# M7104B.net
KiCad netlist of a schematic drawn in EAGLE
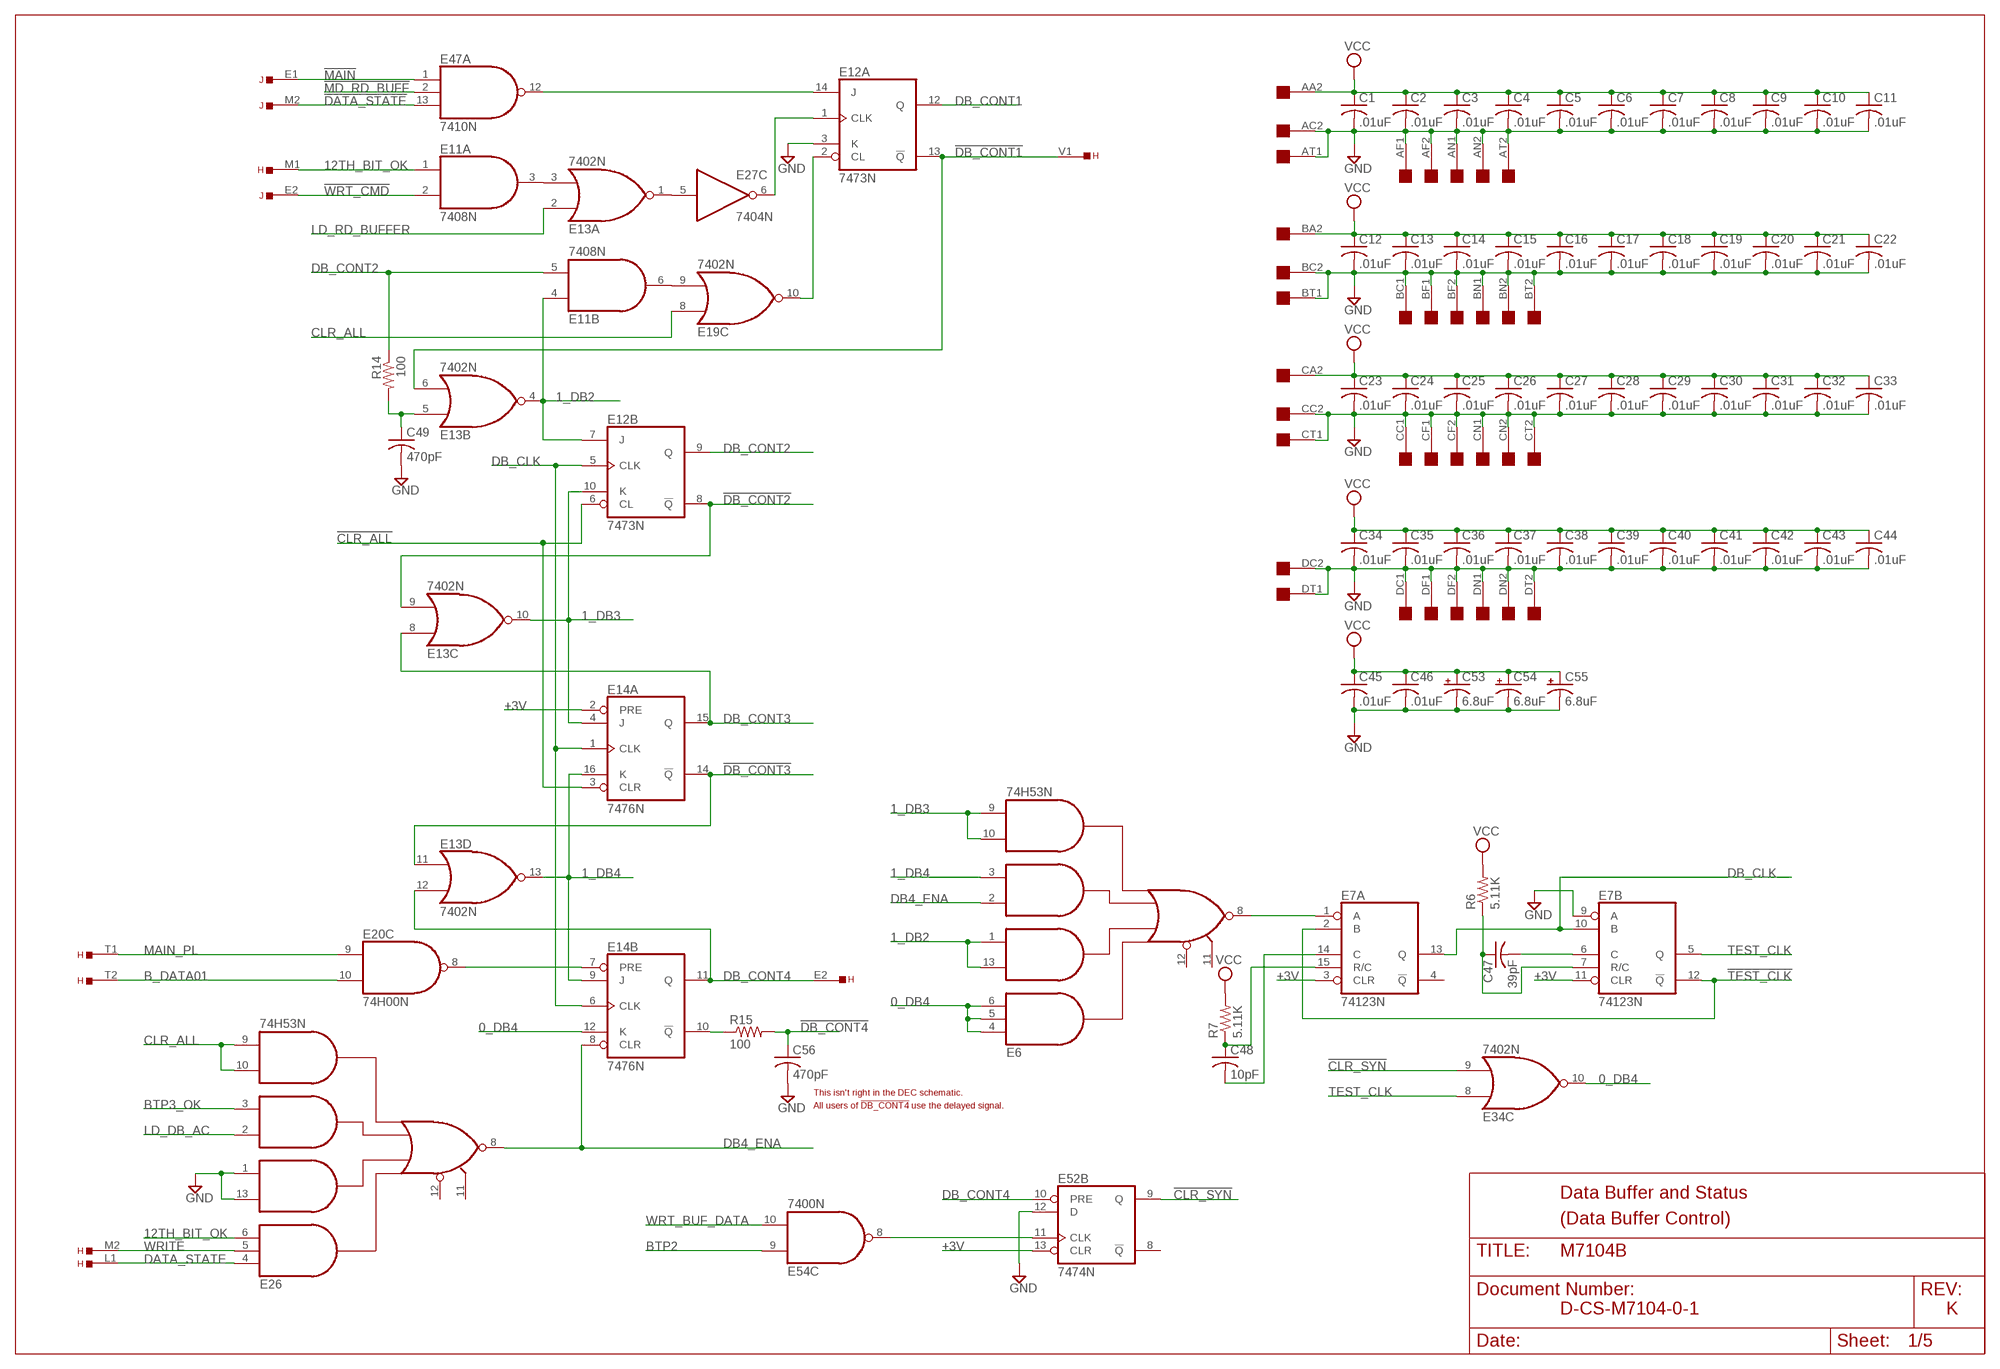
[diagram p0: schematic, sheet 1]
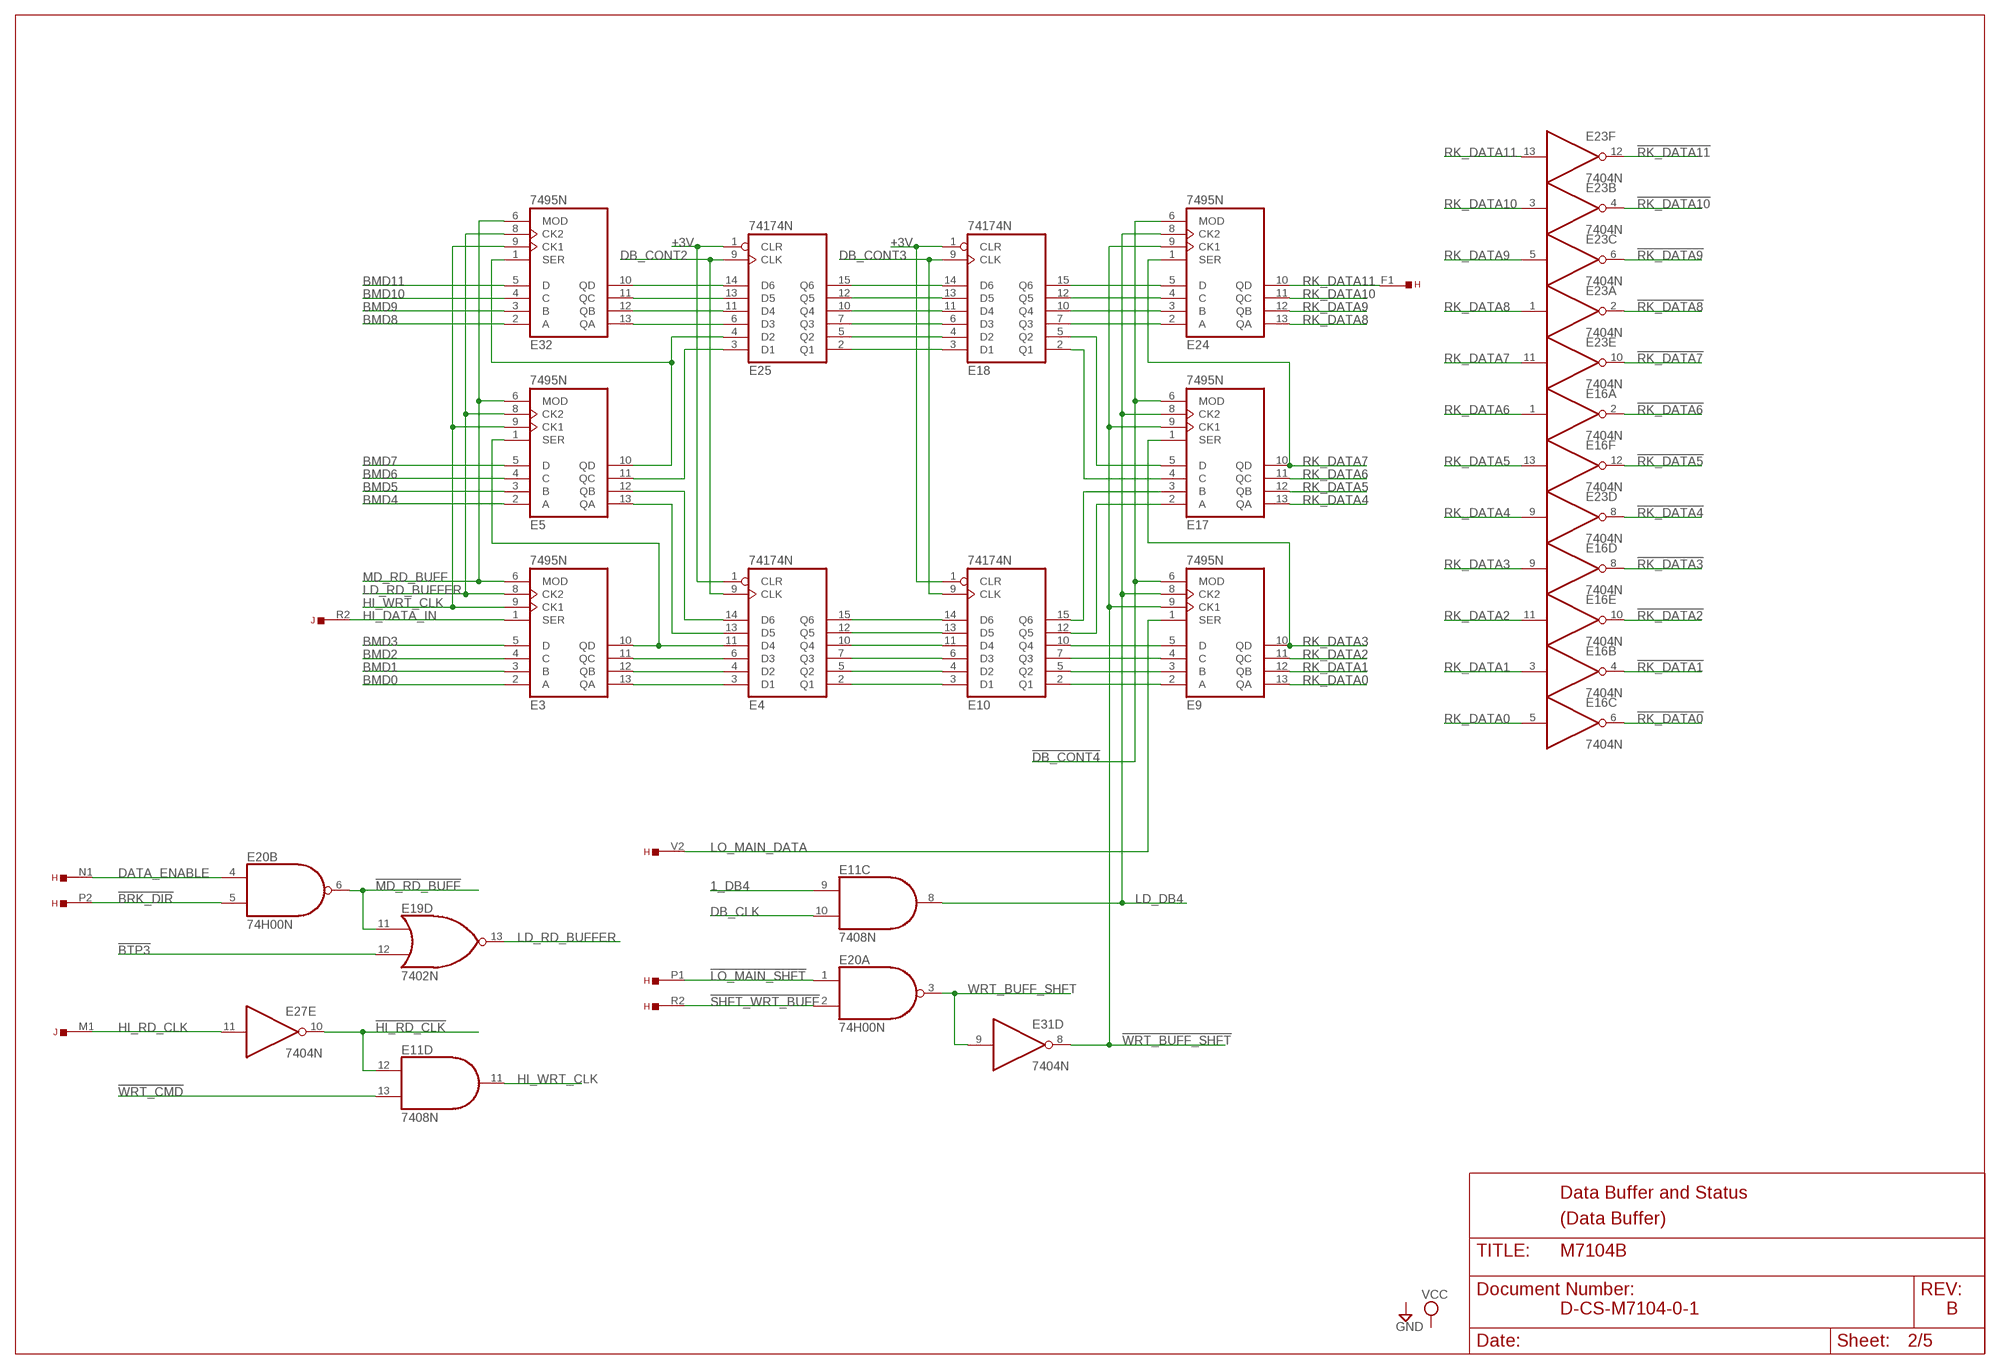
[diagram p1: schematic, sheet 2]
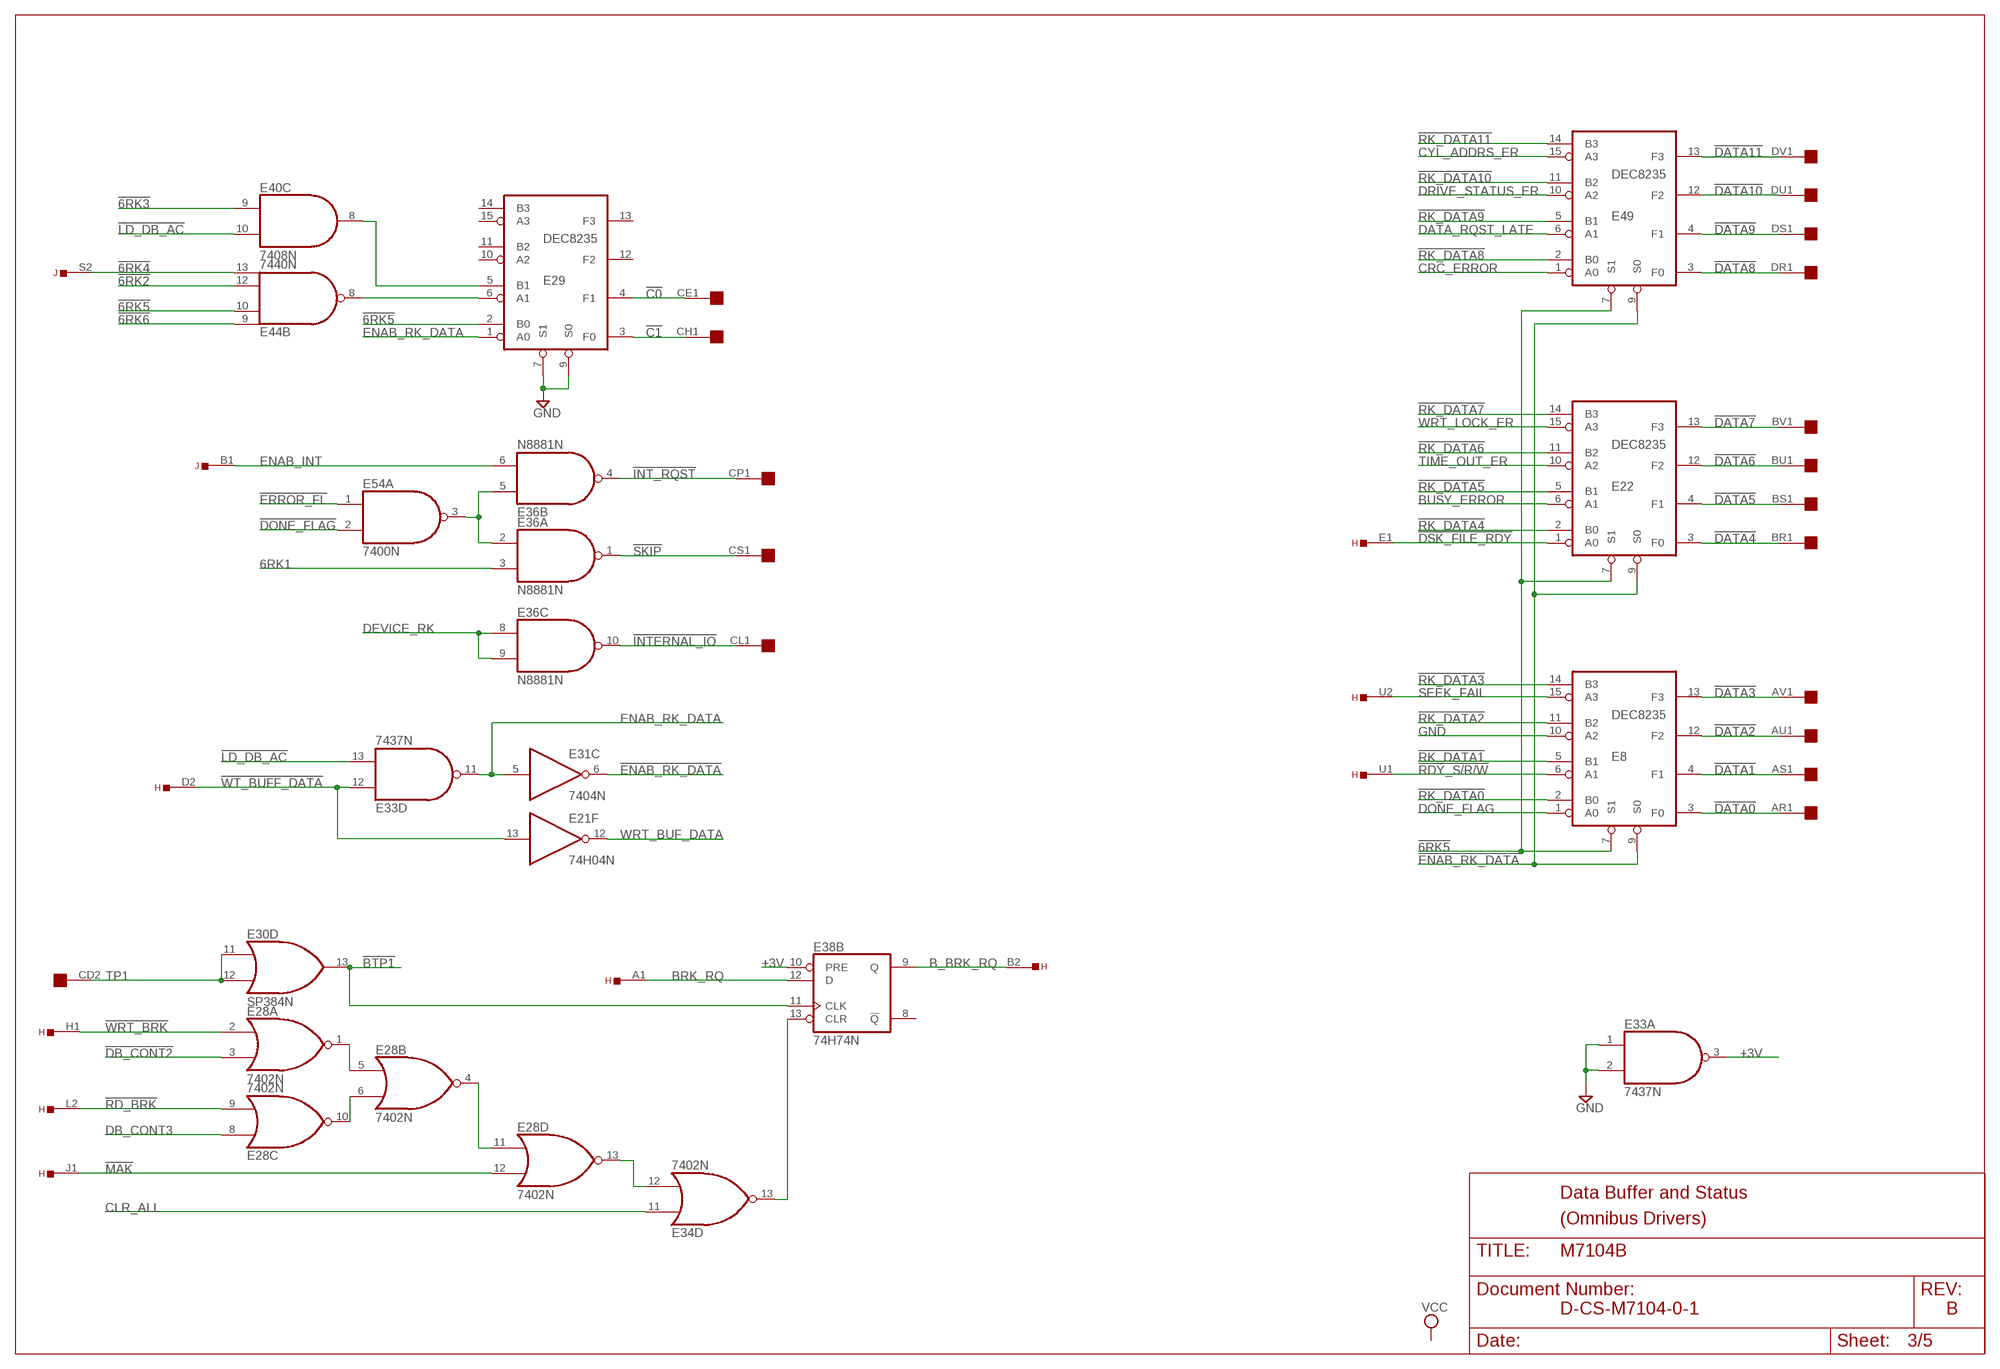
[diagram p2: schematic, sheet 3]
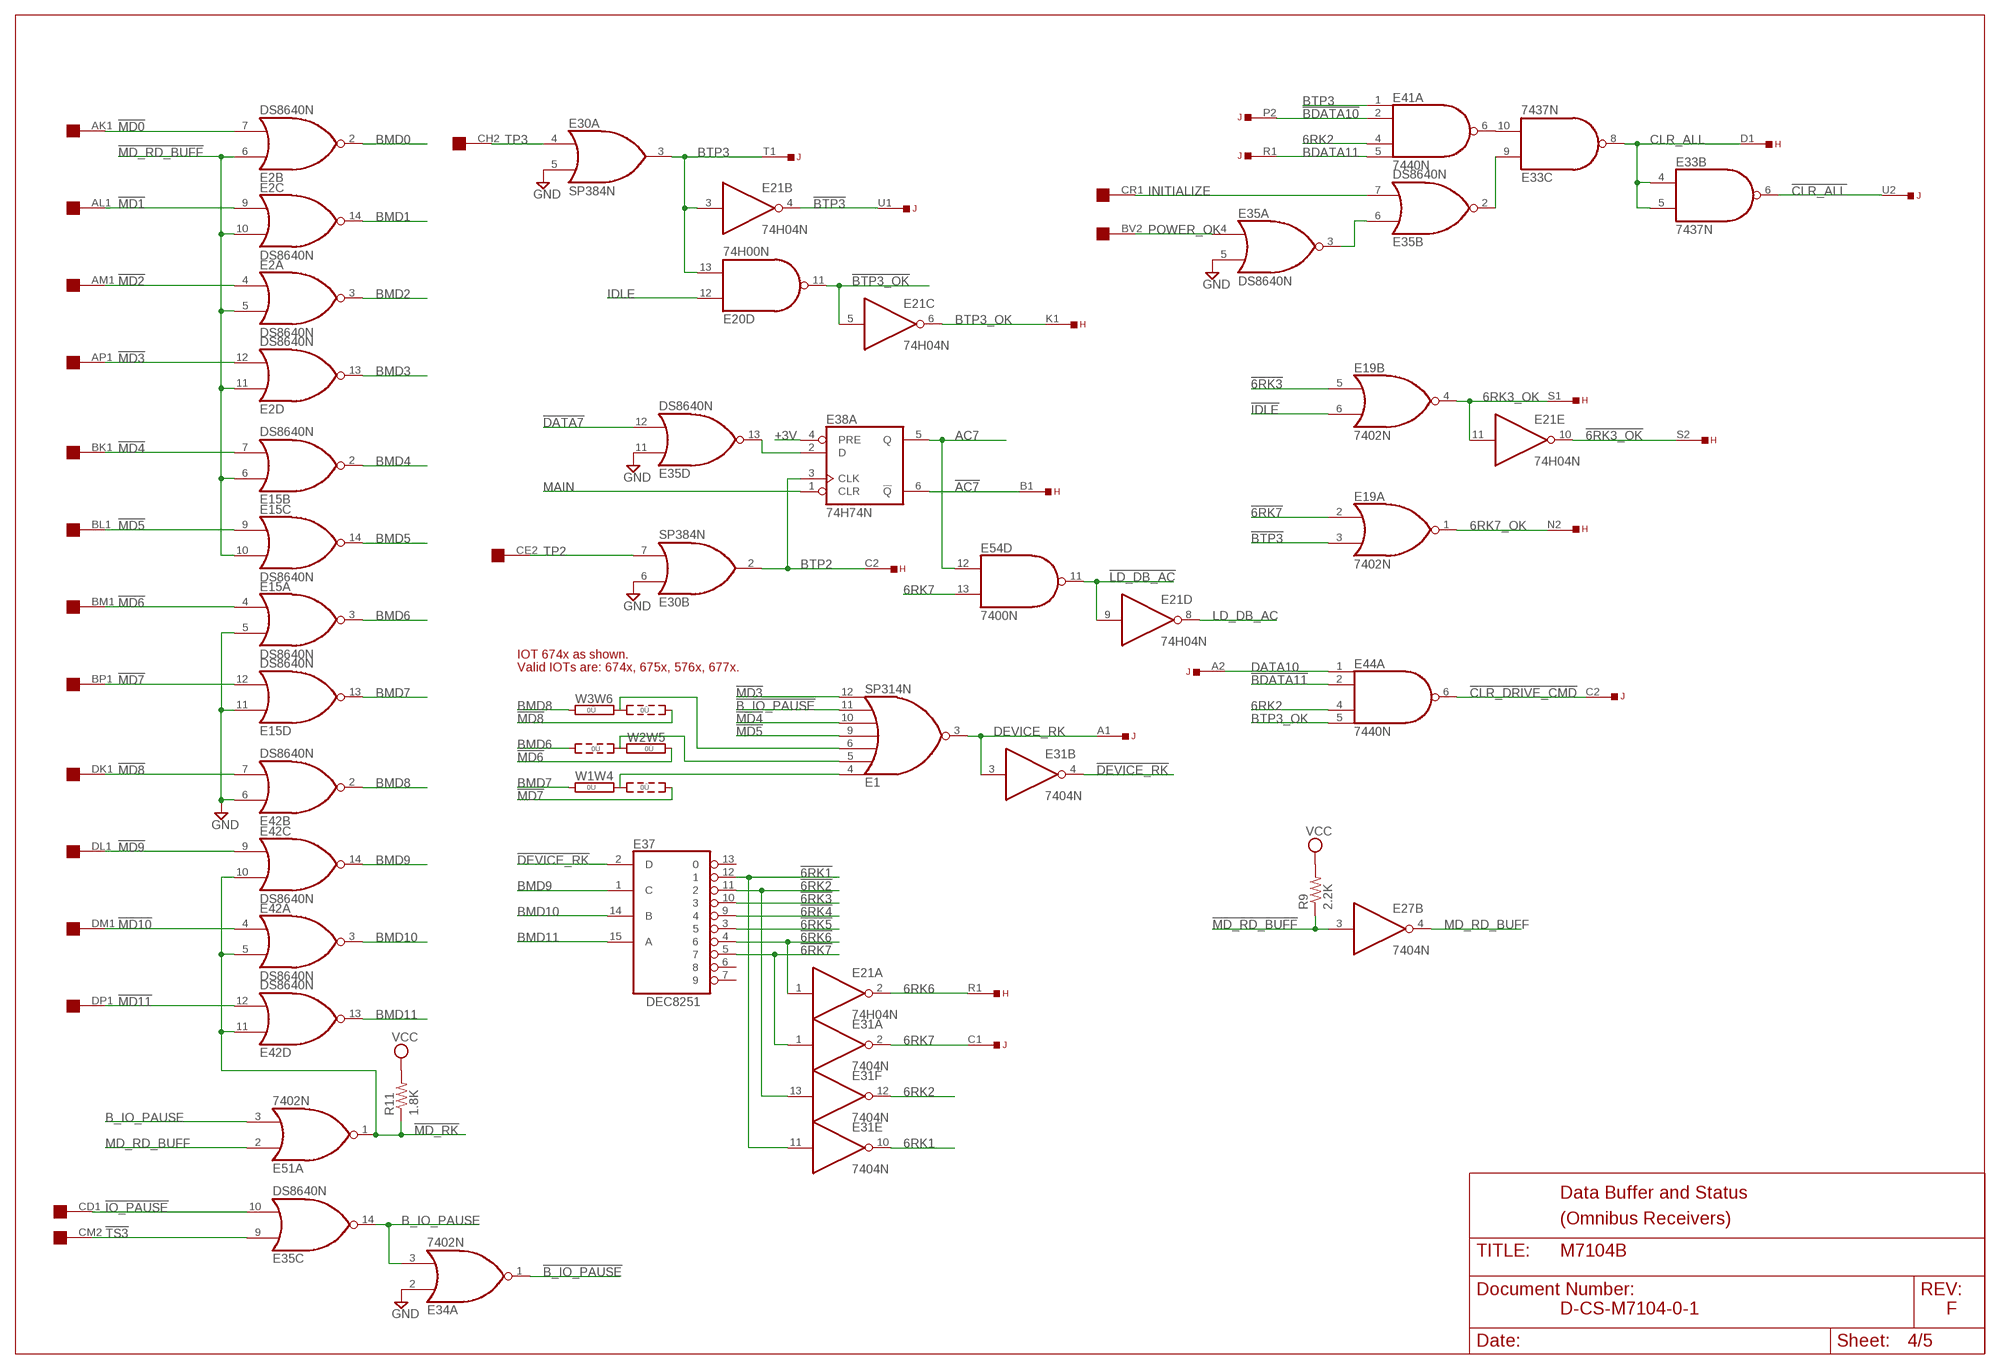
[diagram p3: schematic, sheet 4]
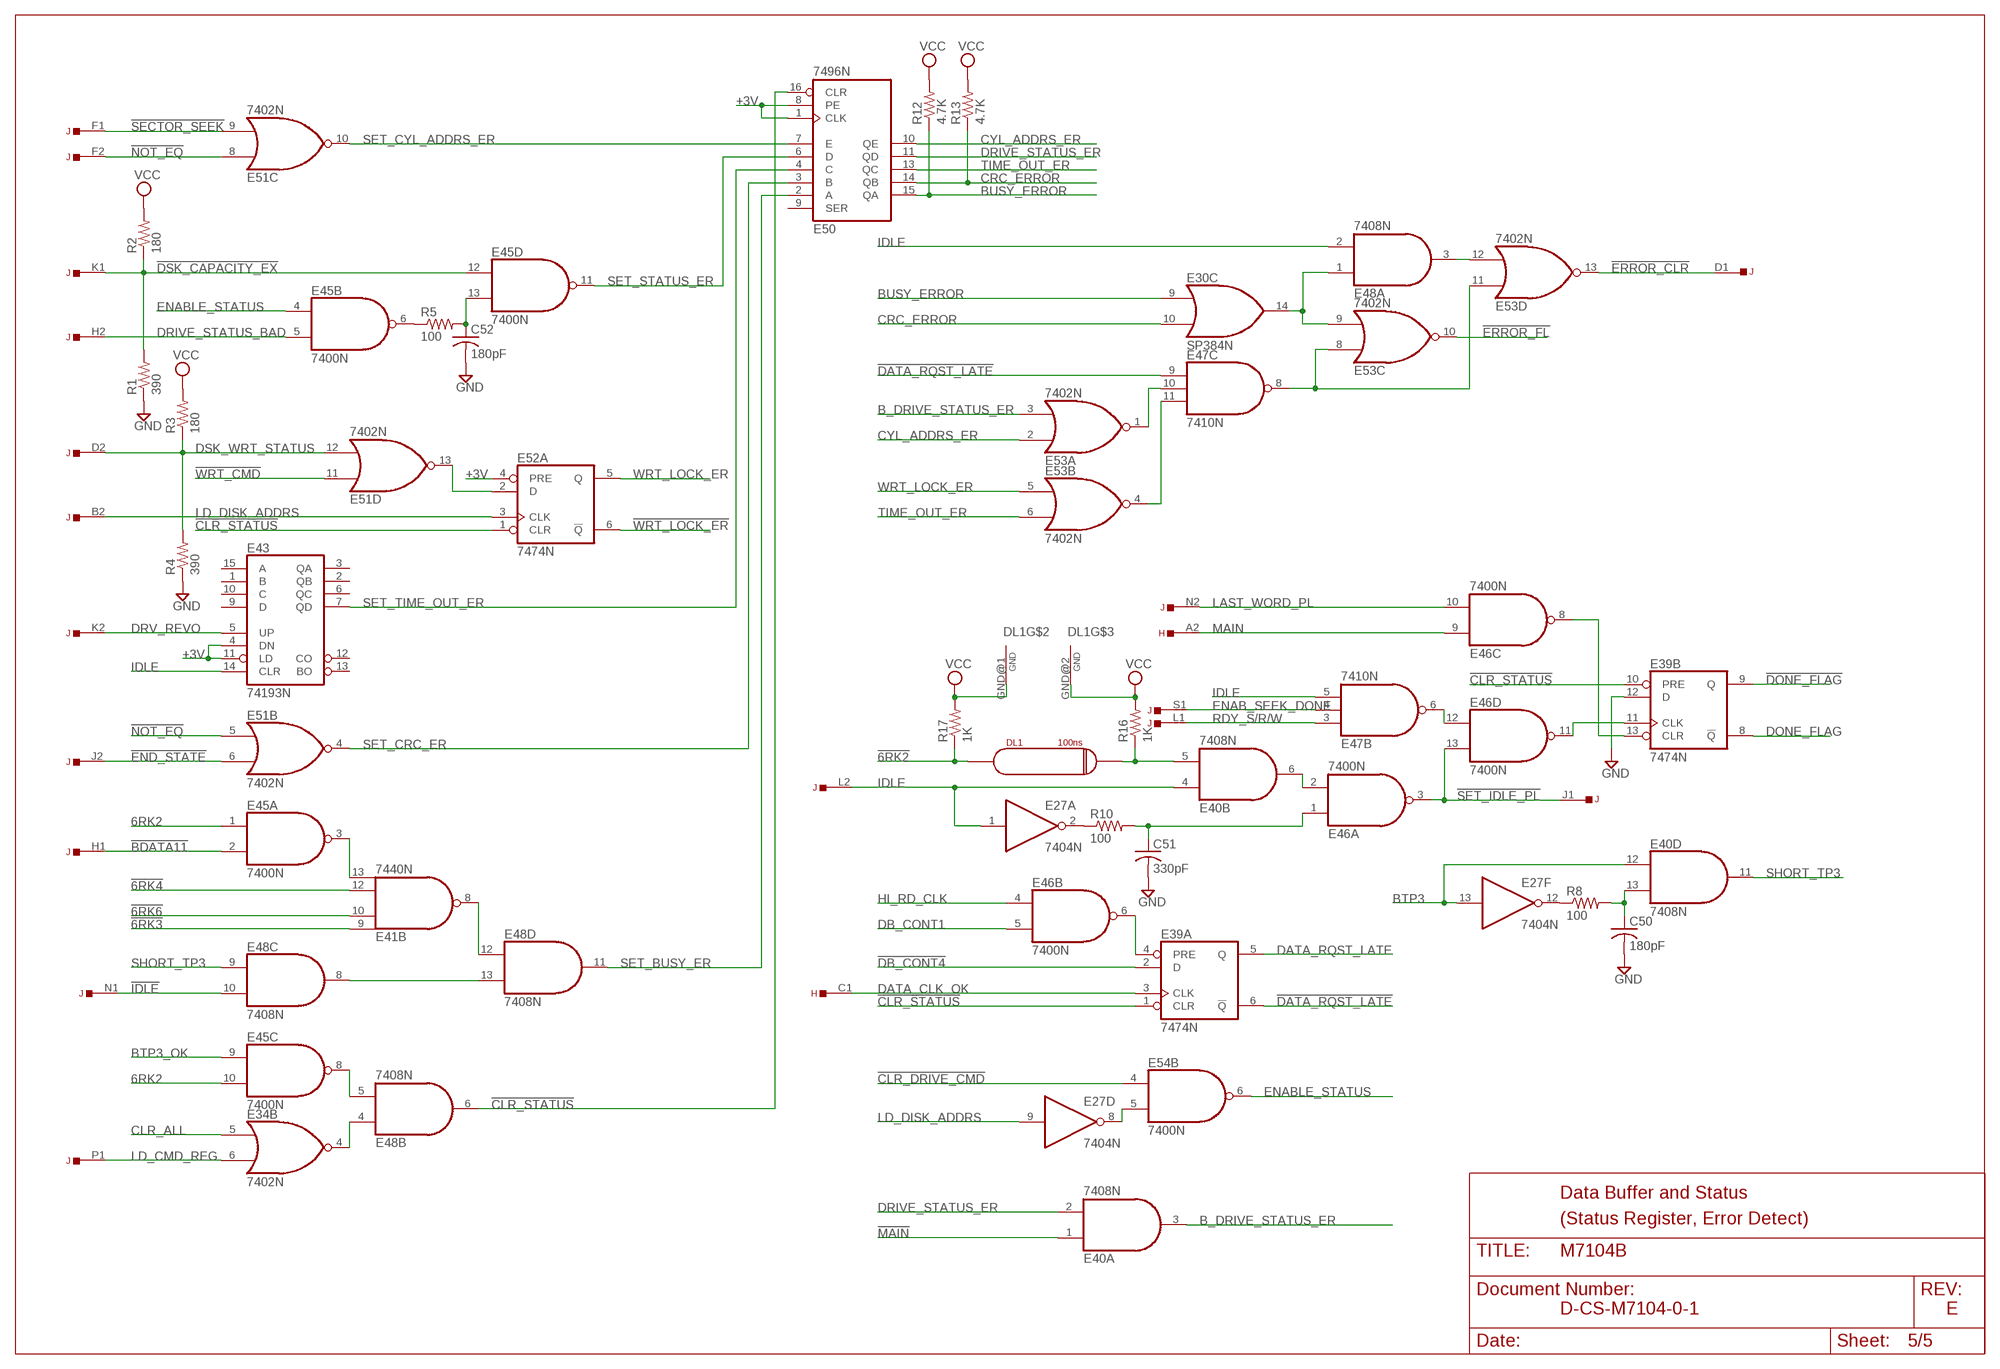
[diagram p4: schematic, sheet 5]

(export (version "E")
  (design (tool "Eeschema 10.0.6"))
  (components
    (comp (ref "C50")
      (value "180pF")
      (footprint "eagle-import:C063-025X075")
      (libsource (lib "eagle-import") (part "C-US"))
    )
    (comp (ref "C51")
      (value "330pF")
      (footprint "eagle-import:C063-025X075")
      (libsource (lib "eagle-import") (part "C-US"))
    )
    (comp (ref "C52")
      (value "180pF")
      (footprint "eagle-import:C063-025X075")
      (libsource (lib "eagle-import") (part "C-US"))
    )
    (comp (ref "DL1")
      (value "100ns")
      (footprint "eagle-import:RCL-L-XX-22")
      (libsource (lib "eagle-import") (part "RC-L-22"))
    )
    (comp (ref "E27")
      (value "7404N")
      (footprint "eagle-import:DIL14")
      (libsource (lib "eagle-import") (part "7404N"))
    )
    (comp (ref "E30")
      (value "SP384N")
      (footprint "eagle-import:DIL14")
      (libsource (lib "eagle-import") (part "SP384N"))
    )
    (comp (ref "E34")
      (value "7402N")
      (footprint "eagle-import:DIL14")
      (libsource (lib "eagle-import") (part "7402N"))
    )
    (comp (ref "E39")
      (value "7474N")
      (footprint "eagle-import:DIL14")
      (libsource (lib "eagle-import") (part "7474NS"))
    )
    (comp (ref "E40")
      (value "7408N")
      (footprint "eagle-import:DIL14")
      (libsource (lib "eagle-import") (part "7408NS"))
    )
    (comp (ref "E41")
      (value "7440N")
      (footprint "eagle-import:DIL14")
      (libsource (lib "eagle-import") (part "7440N"))
    )
    (comp (ref "E43")
      (value "74193N")
      (footprint "eagle-import:DIL16")
      (libsource (lib "eagle-import") (part "74193N"))
    )
    (comp (ref "E45")
      (value "7400N")
      (footprint "eagle-import:DIL14")
      (libsource (lib "eagle-import") (part "7400N"))
    )
    (comp (ref "E46")
      (value "7400N")
      (footprint "eagle-import:DIL14")
      (libsource (lib "eagle-import") (part "7400N"))
    )
    (comp (ref "E47")
      (value "7410N")
      (footprint "eagle-import:DIL14")
      (libsource (lib "eagle-import") (part "7410N"))
    )
    (comp (ref "E48")
      (value "7408N")
      (footprint "eagle-import:DIL14")
      (libsource (lib "eagle-import") (part "7408NS"))
    )
    (comp (ref "E50")
      (value "7496N")
      (footprint "eagle-import:DIL16")
      (libsource (lib "eagle-import") (part "7496NLS"))
    )
    (comp (ref "E51")
      (value "7402N")
      (footprint "eagle-import:DIL14")
      (libsource (lib "eagle-import") (part "7402N"))
    )
    (comp (ref "E52")
      (value "7474N")
      (footprint "eagle-import:DIL14")
      (libsource (lib "eagle-import") (part "7474NS"))
    )
    (comp (ref "E53")
      (value "7402N")
      (footprint "eagle-import:DIL14")
      (libsource (lib "eagle-import") (part "7402N"))
    )
    (comp (ref "E54")
      (value "7400N")
      (footprint "eagle-import:DIL14")
      (libsource (lib "eagle-import") (part "7400N"))
    )
    (comp (ref "H")
      (value "EDGE-TOP")
      (footprint "eagle-import:EDGE-CON2")
      (libsource (lib "eagle-import") (part "EDGE-TOP"))
    )
    (comp (ref "J")
      (value "EDGE-TOP")
      (footprint "eagle-import:EDGE-CON2")
      (libsource (lib "eagle-import") (part "EDGE-TOP"))
    )
    (comp (ref "R1")
      (value "390")
      (footprint "eagle-import:0207_10")
      (libsource (lib "eagle-import") (part "R-US_0207/10"))
    )
    (comp (ref "R2")
      (value "180")
      (footprint "eagle-import:0207_10")
      (libsource (lib "eagle-import") (part "R-US_0207/10"))
    )
    (comp (ref "R3")
      (value "180")
      (footprint "eagle-import:0207_10")
      (libsource (lib "eagle-import") (part "R-US_0207/10"))
    )
    (comp (ref "R4")
      (value "390")
      (footprint "eagle-import:0207_10")
      (libsource (lib "eagle-import") (part "R-US_0207/10"))
    )
    (comp (ref "R5")
      (value "100")
      (footprint "eagle-import:0207_10")
      (libsource (lib "eagle-import") (part "R-US_0207/10"))
    )
    (comp (ref "R8")
      (value "100")
      (footprint "eagle-import:0207_10")
      (libsource (lib "eagle-import") (part "R-US_0207/10"))
    )
    (comp (ref "R10")
      (value "100")
      (footprint "eagle-import:0207_10")
      (libsource (lib "eagle-import") (part "R-US_0207/10"))
    )
    (comp (ref "R12")
      (value "4.7K")
      (footprint "eagle-import:0207_10")
      (libsource (lib "eagle-import") (part "R-US_0207/10"))
    )
    (comp (ref "R13")
      (value "4.7K")
      (footprint "eagle-import:0207_10")
      (libsource (lib "eagle-import") (part "R-US_0207/10"))
    )
    (comp (ref "R16")
      (value "1K")
      (footprint "eagle-import:0207_10")
      (libsource (lib "eagle-import") (part "R-US_0207/10"))
    )
    (comp (ref "R17")
      (value "1K")
      (footprint "eagle-import:0207_10")
      (libsource (lib "eagle-import") (part "R-US_0207/10"))
    )
    (comp (ref "E3")
      (value "7495N")
      (footprint "eagle-import:DIL14")
      (libsource (lib "eagle-import") (part "7495N"))
    )
    (comp (ref "E4")
      (value "74174N")
      (footprint "eagle-import:DIL16")
      (libsource (lib "eagle-import") (part "74174N"))
    )
    (comp (ref "E5")
      (value "7495N")
      (footprint "eagle-import:DIL14")
      (libsource (lib "eagle-import") (part "7495N"))
    )
    (comp (ref "E9")
      (value "7495N")
      (footprint "eagle-import:DIL14")
      (libsource (lib "eagle-import") (part "7495N"))
    )
    (comp (ref "E10")
      (value "74174N")
      (footprint "eagle-import:DIL16")
      (libsource (lib "eagle-import") (part "74174N"))
    )
    (comp (ref "E11")
      (value "7408N")
      (footprint "eagle-import:DIL14")
      (libsource (lib "eagle-import") (part "7408NS"))
    )
    (comp (ref "E16")
      (value "7404N")
      (footprint "eagle-import:DIL14")
      (libsource (lib "eagle-import") (part "7404N"))
    )
    (comp (ref "E17")
      (value "7495N")
      (footprint "eagle-import:DIL14")
      (libsource (lib "eagle-import") (part "7495N"))
    )
    (comp (ref "E18")
      (value "74174N")
      (footprint "eagle-import:DIL16")
      (libsource (lib "eagle-import") (part "74174N"))
    )
    (comp (ref "E19")
      (value "7402N")
      (footprint "eagle-import:DIL14")
      (libsource (lib "eagle-import") (part "7402N"))
    )
    (comp (ref "E20")
      (value "74H00N")
      (footprint "eagle-import:DIL14")
      (libsource (lib "eagle-import") (part "7400NS"))
    )
    (comp (ref "E23")
      (value "7404N")
      (footprint "eagle-import:DIL14")
      (libsource (lib "eagle-import") (part "7404N"))
    )
    (comp (ref "E24")
      (value "7495N")
      (footprint "eagle-import:DIL14")
      (libsource (lib "eagle-import") (part "7495N"))
    )
    (comp (ref "E25")
      (value "74174N")
      (footprint "eagle-import:DIL16")
      (libsource (lib "eagle-import") (part "74174N"))
    )
    (comp (ref "E31")
      (value "7404N")
      (footprint "eagle-import:DIL14")
      (libsource (lib "eagle-import") (part "7404N"))
    )
    (comp (ref "E32")
      (value "7495N")
      (footprint "eagle-import:DIL14")
      (libsource (lib "eagle-import") (part "7495N"))
    )
    (comp (ref "E1")
      (value "SP314N")
      (footprint "eagle-import:DIL14")
      (libsource (lib "eagle-import") (part "SP314N"))
    )
    (comp (ref "E2")
      (value "DS8640N")
      (footprint "eagle-import:DIL14")
      (libsource (lib "eagle-import") (part "DS8640N"))
    )
    (comp (ref "E15")
      (value "DS8640N")
      (footprint "eagle-import:DIL14")
      (libsource (lib "eagle-import") (part "DS8640N"))
    )
    (comp (ref "E21")
      (value "74H04N")
      (footprint "eagle-import:DIL14")
      (libsource (lib "eagle-import") (part "7404N"))
    )
    (comp (ref "E33")
      (value "7437N")
      (footprint "eagle-import:DIL14")
      (libsource (lib "eagle-import") (part "7437N"))
    )
    (comp (ref "E35")
      (value "DS8640N")
      (footprint "eagle-import:DIL14")
      (libsource (lib "eagle-import") (part "DS8640N"))
    )
    (comp (ref "E37")
      (value "DEC8251")
      (footprint "eagle-import:DIL16")
      (libsource (lib "eagle-import") (part "DEC8251"))
    )
    (comp (ref "E38")
      (value "74H74N")
      (footprint "eagle-import:DIL14")
      (libsource (lib "eagle-import") (part "7474NS"))
    )
    (comp (ref "E42")
      (value "DS8640N")
      (footprint "eagle-import:DIL14")
      (libsource (lib "eagle-import") (part "DS8640N"))
    )
    (comp (ref "E44")
      (value "7440N")
      (footprint "eagle-import:DIL14")
      (libsource (lib "eagle-import") (part "7440N"))
    )
    (comp (ref "OMNIBUS")
      (value "QUAD")
      (footprint "eagle-import:EDGE-CON8")
      (libsource (lib "eagle-import") (part "QUAD"))
    )
    (comp (ref "R9")
      (value "2.2K")
      (footprint "eagle-import:0207_10")
      (libsource (lib "eagle-import") (part "R-US_0207/10"))
    )
    (comp (ref "R11")
      (value "1.8K")
      (footprint "eagle-import:0207_10")
      (libsource (lib "eagle-import") (part "R-US_0207/10"))
    )
    (comp (ref "W1W4")
      (value "0R2")
      (footprint "eagle-import:0R2_10")
      (libsource (lib "eagle-import") (part "0R2"))
    )
    (comp (ref "W2W5")
      (value "0R2")
      (footprint "eagle-import:0R2_10")
      (libsource (lib "eagle-import") (part "0R2"))
    )
    (comp (ref "W3W6")
      (value "0R2")
      (footprint "eagle-import:0R2_10")
      (libsource (lib "eagle-import") (part "0R2"))
    )
    (comp (ref "C1")
      (value ".01uF")
      (footprint "eagle-import:C063-025X075")
      (libsource (lib "eagle-import") (part "C-US"))
    )
    (comp (ref "C2")
      (value ".01uF")
      (footprint "eagle-import:C063-025X075")
      (libsource (lib "eagle-import") (part "C-US"))
    )
    (comp (ref "C3")
      (value ".01uF")
      (footprint "eagle-import:C063-025X075")
      (libsource (lib "eagle-import") (part "C-US"))
    )
    (comp (ref "C4")
      (value ".01uF")
      (footprint "eagle-import:C063-025X075")
      (libsource (lib "eagle-import") (part "C-US"))
    )
    (comp (ref "C5")
      (value ".01uF")
      (footprint "eagle-import:C063-025X075")
      (libsource (lib "eagle-import") (part "C-US"))
    )
    (comp (ref "C6")
      (value ".01uF")
      (footprint "eagle-import:C063-025X075")
      (libsource (lib "eagle-import") (part "C-US"))
    )
    (comp (ref "C7")
      (value ".01uF")
      (footprint "eagle-import:C063-025X075")
      (libsource (lib "eagle-import") (part "C-US"))
    )
    (comp (ref "C8")
      (value ".01uF")
      (footprint "eagle-import:C063-025X075")
      (libsource (lib "eagle-import") (part "C-US"))
    )
    (comp (ref "C9")
      (value ".01uF")
      (footprint "eagle-import:C063-025X075")
      (libsource (lib "eagle-import") (part "C-US"))
    )
    (comp (ref "C10")
      (value ".01uF")
      (footprint "eagle-import:C063-025X075")
      (libsource (lib "eagle-import") (part "C-US"))
    )
    (comp (ref "C11")
      (value ".01uF")
      (footprint "eagle-import:C063-025X075")
      (libsource (lib "eagle-import") (part "C-US"))
    )
    (comp (ref "C12")
      (value ".01uF")
      (footprint "eagle-import:C063-025X075")
      (libsource (lib "eagle-import") (part "C-US"))
    )
    (comp (ref "C13")
      (value ".01uF")
      (footprint "eagle-import:C063-025X075")
      (libsource (lib "eagle-import") (part "C-US"))
    )
    (comp (ref "C14")
      (value ".01uF")
      (footprint "eagle-import:C063-025X075")
      (libsource (lib "eagle-import") (part "C-US"))
    )
    (comp (ref "C15")
      (value ".01uF")
      (footprint "eagle-import:C063-025X075")
      (libsource (lib "eagle-import") (part "C-US"))
    )
    (comp (ref "C16")
      (value ".01uF")
      (footprint "eagle-import:C063-025X075")
      (libsource (lib "eagle-import") (part "C-US"))
    )
    (comp (ref "C17")
      (value ".01uF")
      (footprint "eagle-import:C063-025X075")
      (libsource (lib "eagle-import") (part "C-US"))
    )
    (comp (ref "C18")
      (value ".01uF")
      (footprint "eagle-import:C063-025X075")
      (libsource (lib "eagle-import") (part "C-US"))
    )
    (comp (ref "C19")
      (value ".01uF")
      (footprint "eagle-import:C063-025X075")
      (libsource (lib "eagle-import") (part "C-US"))
    )
    (comp (ref "C20")
      (value ".01uF")
      (footprint "eagle-import:C063-025X075")
      (libsource (lib "eagle-import") (part "C-US"))
    )
    (comp (ref "C21")
      (value ".01uF")
      (footprint "eagle-import:C063-025X075")
      (libsource (lib "eagle-import") (part "C-US"))
    )
    (comp (ref "C22")
      (value ".01uF")
      (footprint "eagle-import:C063-025X075")
      (libsource (lib "eagle-import") (part "C-US"))
    )
    (comp (ref "C23")
      (value ".01uF")
      (footprint "eagle-import:C063-025X075")
      (libsource (lib "eagle-import") (part "C-US"))
    )
    (comp (ref "C24")
      (value ".01uF")
      (footprint "eagle-import:C063-025X075")
      (libsource (lib "eagle-import") (part "C-US"))
    )
    (comp (ref "C25")
      (value ".01uF")
      (footprint "eagle-import:C063-025X075")
      (libsource (lib "eagle-import") (part "C-US"))
    )
    (comp (ref "C26")
      (value ".01uF")
      (footprint "eagle-import:C063-025X075")
      (libsource (lib "eagle-import") (part "C-US"))
    )
    (comp (ref "C27")
      (value ".01uF")
      (footprint "eagle-import:C063-025X075")
      (libsource (lib "eagle-import") (part "C-US"))
    )
    (comp (ref "C28")
      (value ".01uF")
      (footprint "eagle-import:C063-025X075")
      (libsource (lib "eagle-import") (part "C-US"))
    )
    (comp (ref "C29")
      (value ".01uF")
      (footprint "eagle-import:C063-025X075")
      (libsource (lib "eagle-import") (part "C-US"))
    )
    (comp (ref "C30")
      (value ".01uF")
      (footprint "eagle-import:C063-025X075")
      (libsource (lib "eagle-import") (part "C-US"))
    )
    (comp (ref "C31")
      (value ".01uF")
      (footprint "eagle-import:C063-025X075")
      (libsource (lib "eagle-import") (part "C-US"))
    )
    (comp (ref "C32")
      (value ".01uF")
      (footprint "eagle-import:C063-025X075")
      (libsource (lib "eagle-import") (part "C-US"))
    )
    (comp (ref "C33")
      (value ".01uF")
      (footprint "eagle-import:C063-025X075")
      (libsource (lib "eagle-import") (part "C-US"))
    )
    (comp (ref "C34")
      (value ".01uF")
      (footprint "eagle-import:C063-025X075")
      (libsource (lib "eagle-import") (part "C-US"))
    )
    (comp (ref "C35")
      (value ".01uF")
      (footprint "eagle-import:C063-025X075")
      (libsource (lib "eagle-import") (part "C-US"))
    )
    (comp (ref "C36")
      (value ".01uF")
      (footprint "eagle-import:C063-025X075")
      (libsource (lib "eagle-import") (part "C-US"))
    )
    (comp (ref "C37")
      (value ".01uF")
      (footprint "eagle-import:C063-025X075")
      (libsource (lib "eagle-import") (part "C-US"))
    )
    (comp (ref "C38")
      (value ".01uF")
      (footprint "eagle-import:C063-025X075")
      (libsource (lib "eagle-import") (part "C-US"))
    )
    (comp (ref "C39")
      (value ".01uF")
      (footprint "eagle-import:C063-025X075")
      (libsource (lib "eagle-import") (part "C-US"))
    )
    (comp (ref "C40")
      (value ".01uF")
      (footprint "eagle-import:C063-025X075")
      (libsource (lib "eagle-import") (part "C-US"))
    )
    (comp (ref "C41")
      (value ".01uF")
      (footprint "eagle-import:C063-025X075")
      (libsource (lib "eagle-import") (part "C-US"))
    )
    (comp (ref "C42")
      (value ".01uF")
      (footprint "eagle-import:C063-025X075")
      (libsource (lib "eagle-import") (part "C-US"))
    )
    (comp (ref "C43")
      (value ".01uF")
      (footprint "eagle-import:C063-025X075")
      (libsource (lib "eagle-import") (part "C-US"))
    )
    (comp (ref "C44")
      (value ".01uF")
      (footprint "eagle-import:C063-025X075")
      (libsource (lib "eagle-import") (part "C-US"))
    )
    (comp (ref "C45")
      (value ".01uF")
      (footprint "eagle-import:C063-025X075")
      (libsource (lib "eagle-import") (part "C-US"))
    )
    (comp (ref "C46")
      (value ".01uF")
      (footprint "eagle-import:C063-025X075")
      (libsource (lib "eagle-import") (part "C-US"))
    )
    (comp (ref "C47")
      (value "39pF")
      (footprint "eagle-import:C063-025X075")
      (libsource (lib "eagle-import") (part "C-US"))
    )
    (comp (ref "C48")
      (value "10pF")
      (footprint "eagle-import:C063-025X075")
      (libsource (lib "eagle-import") (part "C-US"))
    )
    (comp (ref "C49")
      (value "470pF")
      (footprint "eagle-import:C063-025X075")
      (libsource (lib "eagle-import") (part "C-US"))
    )
    (comp (ref "C53")
      (value "6.8uF")
      (footprint "eagle-import:E12-8")
      (libsource (lib "eagle-import") (part "CPOL-USE20-8AXIAL"))
    )
    (comp (ref "C54")
      (value "6.8uF")
      (footprint "eagle-import:E12-8")
      (libsource (lib "eagle-import") (part "CPOL-USE20-8AXIAL"))
    )
    (comp (ref "C55")
      (value "6.8uF")
      (footprint "eagle-import:E12-8")
      (libsource (lib "eagle-import") (part "CPOL-USE20-8AXIAL"))
    )
    (comp (ref "C56")
      (value "470pF")
      (footprint "eagle-import:C063-025X075")
      (libsource (lib "eagle-import") (part "C-US"))
    )
    (comp (ref "E6")
      (value "74H53N")
      (footprint "eagle-import:DIL14")
      (libsource (lib "eagle-import") (part "74H53N"))
    )
    (comp (ref "E7")
      (value "74123N")
      (footprint "eagle-import:DIL16")
      (libsource (lib "eagle-import") (part "74123N"))
    )
    (comp (ref "E12")
      (value "7473N")
      (footprint "eagle-import:DIL14")
      (libsource (lib "eagle-import") (part "7473NLS"))
    )
    (comp (ref "E13")
      (value "7402N")
      (footprint "eagle-import:DIL14")
      (libsource (lib "eagle-import") (part "7402N"))
    )
    (comp (ref "E14")
      (value "7476N")
      (footprint "eagle-import:DIL16")
      (libsource (lib "eagle-import") (part "7476N"))
    )
    (comp (ref "E26")
      (value "74H53N")
      (footprint "eagle-import:DIL14")
      (libsource (lib "eagle-import") (part "74H53N"))
    )
    (comp (ref "R6")
      (value "5.11K")
      (footprint "eagle-import:0207_15")
      (libsource (lib "eagle-import") (part "R-US_0207/15"))
    )
    (comp (ref "R7")
      (value "5.11K")
      (footprint "eagle-import:0207_15")
      (libsource (lib "eagle-import") (part "R-US_0207/15"))
    )
    (comp (ref "R14")
      (value "100")
      (footprint "eagle-import:0207_10")
      (libsource (lib "eagle-import") (part "R-US_0207/10"))
    )
    (comp (ref "R15")
      (value "100")
      (footprint "eagle-import:0207_10")
      (libsource (lib "eagle-import") (part "R-US_0207/10"))
    )
    (comp (ref "E8")
      (value "DEC8235")
      (footprint "eagle-import:DIL16")
      (libsource (lib "eagle-import") (part "DEC8235"))
    )
    (comp (ref "E22")
      (value "DEC8235")
      (footprint "eagle-import:DIL16")
      (libsource (lib "eagle-import") (part "DEC8235"))
    )
    (comp (ref "E28")
      (value "7402N")
      (footprint "eagle-import:DIL14")
      (libsource (lib "eagle-import") (part "7402N"))
    )
    (comp (ref "E29")
      (value "DEC8235")
      (footprint "eagle-import:DIL16")
      (libsource (lib "eagle-import") (part "DEC8235"))
    )
    (comp (ref "E36")
      (value "N8881N")
      (footprint "eagle-import:DIL14")
      (libsource (lib "eagle-import") (part "N8881N"))
    )
    (comp (ref "E49")
      (value "DEC8235")
      (footprint "eagle-import:DIL16")
      (libsource (lib "eagle-import") (part "DEC8235"))
    )
  )
  (nets
    (net (code "1") (name "+3V") (class "Default")
      (node (ref "E10") (pin "1") (pinfunction "CLR_1") (pintype "input"))
      (node (ref "E14") (pin "2") (pinfunction "PRE_2") (pintype "input"))
      (node (ref "E18") (pin "1") (pinfunction "CLR_1") (pintype "input"))
      (node (ref "E25") (pin "1") (pinfunction "CLR_1") (pintype "input"))
      (node (ref "E33") (pin "3") (pinfunction "O_3") (pintype "output"))
      (node (ref "E38") (pin "10") (pinfunction "PRE_10") (pintype "input"))
      (node (ref "E38") (pin "4") (pinfunction "PRE_4") (pintype "input"))
      (node (ref "E4") (pin "1") (pinfunction "CLR_1") (pintype "input"))
      (node (ref "E43") (pin "11") (pinfunction "LD_11") (pintype "input"))
      (node (ref "E43") (pin "4") (pinfunction "DN_4") (pintype "input"))
      (node (ref "E50") (pin "1") (pinfunction "CLK_1") (pintype "input"))
      (node (ref "E50") (pin "8") (pinfunction "PE_8") (pintype "input"))
      (node (ref "E52") (pin "13") (pinfunction "CLR_13") (pintype "input"))
      (node (ref "E52") (pin "4") (pinfunction "PRE_4") (pintype "input"))
      (node (ref "E7") (pin "11") (pinfunction "CLR_11") (pintype "input"))
      (node (ref "E7") (pin "3") (pinfunction "CLR_3") (pintype "input"))
    )
    (net (code "2") (name "0_DB4") (class "Default")
      (node (ref "E14") (pin "12") (pinfunction "K_12") (pintype "input"))
      (node (ref "E34") (pin "10") (pinfunction "O_10") (pintype "output"))
      (node (ref "E6") (pin "4") (pinfunction "I1_4") (pintype "input"))
      (node (ref "E6") (pin "5") (pinfunction "I11_5") (pintype "input"))
      (node (ref "E6") (pin "6") (pinfunction "I2_6") (pintype "input"))
    )
    (net (code "3") (name "1_DB2") (class "Default")
      (node (ref "E11") (pin "4") (pinfunction "I0_4") (pintype "input"))
      (node (ref "E12") (pin "7") (pinfunction "J_7") (pintype "input"))
      (node (ref "E13") (pin "4") (pinfunction "O_4") (pintype "output"))
      (node (ref "E6") (pin "1") (pinfunction "I4_1") (pintype "input"))
      (node (ref "E6") (pin "13") (pinfunction "I3_13") (pintype "input"))
    )
    (net (code "4") (name "1_DB3") (class "Default")
      (node (ref "E12") (pin "10") (pinfunction "K_10") (pintype "input"))
      (node (ref "E13") (pin "10") (pinfunction "O_10") (pintype "output"))
      (node (ref "E14") (pin "4") (pinfunction "J_4") (pintype "input"))
      (node (ref "E6") (pin "10") (pinfunction "I7_10") (pintype "input"))
      (node (ref "E6") (pin "9") (pinfunction "I8_9") (pintype "input"))
    )
    (net (code "5") (name "1_DB4") (class "Default")
      (node (ref "E11") (pin "9") (pinfunction "I0_9") (pintype "input"))
      (node (ref "E13") (pin "13") (pinfunction "O_13") (pintype "output"))
      (node (ref "E14") (pin "16") (pinfunction "K_16") (pintype "input"))
      (node (ref "E14") (pin "9") (pinfunction "J_9") (pintype "input"))
      (node (ref "E6") (pin "3") (pinfunction "I6_3") (pintype "input"))
    )
    (net (code "6") (name "6RK1") (class "Default")
      (node (ref "E31") (pin "10") (pinfunction "O_10") (pintype "output"))
      (node (ref "E36") (pin "3") (pinfunction "I1_3") (pintype "input"))
    )
    (net (code "7") (name "6RK2") (class "Default")
      (node (ref "E31") (pin "12") (pinfunction "O_12") (pintype "output"))
      (node (ref "E41") (pin "4") (pinfunction "I2_4") (pintype "input"))
      (node (ref "E44") (pin "4") (pinfunction "I2_4") (pintype "input"))
      (node (ref "E45") (pin "1") (pinfunction "I0_1") (pintype "input"))
      (node (ref "E45") (pin "10") (pinfunction "I1_10") (pintype "input"))
    )
    (net (code "8") (name "6RK3_OK") (class "Default")
      (node (ref "E19") (pin "4") (pinfunction "O_4") (pintype "output"))
      (node (ref "E21") (pin "11") (pinfunction "I_11") (pintype "input"))
      (node (ref "H") (pin "S1") (pinfunction "P_S1") (pintype "passive"))
    )
    (net (code "9") (name "6RK6") (class "Default")
      (node (ref "E21") (pin "2") (pinfunction "O_2") (pintype "output"))
      (node (ref "H") (pin "R1") (pinfunction "P_R1") (pintype "passive"))
    )
    (net (code "10") (name "6RK7") (class "Default")
      (node (ref "E31") (pin "2") (pinfunction "O_2") (pintype "output"))
      (node (ref "E54") (pin "13") (pinfunction "I1_13") (pintype "input"))
      (node (ref "J") (pin "C1") (pinfunction "P_C1") (pintype "passive"))
    )
    (net (code "11") (name "6RK7_OK") (class "Default")
      (node (ref "E19") (pin "1") (pinfunction "O_1") (pintype "output"))
      (node (ref "H") (pin "N2") (pinfunction "P_N2") (pintype "passive"))
    )
    (net (code "12") (name "12TH_BIT_OK") (class "Default")
      (node (ref "E11") (pin "1") (pinfunction "I0_1") (pintype "input"))
      (node (ref "E26") (pin "6") (pinfunction "I2_6") (pintype "input"))
      (node (ref "H") (pin "M1") (pinfunction "P_M1") (pintype "passive"))
    )
    (net (code "13") (name "AC7") (class "Default")
      (node (ref "E38") (pin "5") (pinfunction "Q_5") (pintype "output"))
      (node (ref "E54") (pin "12") (pinfunction "I0_12") (pintype "input"))
    )
    (net (code "14") (name "BDATA11") (class "Default")
      (node (ref "E41") (pin "5") (pinfunction "I3_5") (pintype "input"))
      (node (ref "J") (pin "R1") (pinfunction "P_R1") (pintype "passive"))
    )
    (net (code "15") (name "BMD0") (class "Default")
      (node (ref "E2") (pin "2") (pinfunction "O_2") (pintype "output"))
      (node (ref "E3") (pin "2") (pinfunction "A_2") (pintype "input"))
    )
    (net (code "16") (name "BMD1") (class "Default")
      (node (ref "E2") (pin "14") (pinfunction "O_14") (pintype "output"))
      (node (ref "E3") (pin "3") (pinfunction "B_3") (pintype "input"))
    )
    (net (code "17") (name "BMD2") (class "Default")
      (node (ref "E2") (pin "3") (pinfunction "O_3") (pintype "output"))
      (node (ref "E3") (pin "4") (pinfunction "C_4") (pintype "input"))
    )
    (net (code "18") (name "BMD3") (class "Default")
      (node (ref "E2") (pin "13") (pinfunction "O_13") (pintype "output"))
      (node (ref "E3") (pin "5") (pinfunction "D_5") (pintype "input"))
    )
    (net (code "19") (name "BMD4") (class "Default")
      (node (ref "E15") (pin "2") (pinfunction "O_2") (pintype "output"))
      (node (ref "E5") (pin "2") (pinfunction "A_2") (pintype "input"))
    )
    (net (code "20") (name "BMD5") (class "Default")
      (node (ref "E15") (pin "14") (pinfunction "O_14") (pintype "output"))
      (node (ref "E5") (pin "3") (pinfunction "B_3") (pintype "input"))
    )
    (net (code "21") (name "BMD6") (class "Default")
      (node (ref "E15") (pin "3") (pinfunction "O_3") (pintype "output"))
      (node (ref "E5") (pin "4") (pinfunction "C_4") (pintype "input"))
      (node (ref "W2W5") (pin "3") (pinfunction "3_3") (pintype "passive"))
    )
    (net (code "22") (name "BMD7") (class "Default")
      (node (ref "E15") (pin "13") (pinfunction "O_13") (pintype "output"))
      (node (ref "E5") (pin "5") (pinfunction "D_5") (pintype "input"))
      (node (ref "W1W4") (pin "1") (pinfunction "1_1") (pintype "passive"))
    )
    (net (code "23") (name "BMD8") (class "Default")
      (node (ref "E32") (pin "2") (pinfunction "A_2") (pintype "input"))
      (node (ref "E42") (pin "2") (pinfunction "O_2") (pintype "output"))
      (node (ref "W3W6") (pin "1") (pinfunction "1_1") (pintype "passive"))
    )
    (net (code "24") (name "BMD9") (class "Default")
      (node (ref "E32") (pin "3") (pinfunction "B_3") (pintype "input"))
      (node (ref "E37") (pin "1") (pinfunction "C_1") (pintype "input"))
      (node (ref "E42") (pin "14") (pinfunction "O_14") (pintype "output"))
    )
    (net (code "25") (name "BMD10") (class "Default")
      (node (ref "E32") (pin "4") (pinfunction "C_4") (pintype "input"))
      (node (ref "E37") (pin "14") (pinfunction "B_14") (pintype "input"))
      (node (ref "E42") (pin "3") (pinfunction "O_3") (pintype "output"))
    )
    (net (code "26") (name "BMD11") (class "Default")
      (node (ref "E32") (pin "5") (pinfunction "D_5") (pintype "input"))
      (node (ref "E37") (pin "15") (pinfunction "A_15") (pintype "input"))
      (node (ref "E42") (pin "13") (pinfunction "O_13") (pintype "output"))
    )
    (net (code "27") (name "BRK_RQ") (class "Default")
      (node (ref "E38") (pin "12") (pinfunction "D_12") (pintype "input"))
      (node (ref "H") (pin "A1") (pinfunction "P_A1") (pintype "passive"))
    )
    (net (code "28") (name "BTP2") (class "Default")
      (node (ref "E30") (pin "2") (pinfunction "O_2") (pintype "output"))
      (node (ref "E38") (pin "3") (pinfunction "CLK_3") (pintype "input"))
      (node (ref "E54") (pin "9") (pinfunction "I0_9") (pintype "input"))
      (node (ref "H") (pin "C2") (pinfunction "P_C2") (pintype "passive"))
    )
    (net (code "29") (name "BTP3") (class "Default")
      (node (ref "E20") (pin "13") (pinfunction "I1_13") (pintype "input"))
      (node (ref "E21") (pin "3") (pinfunction "I_3") (pintype "input"))
      (node (ref "E27") (pin "13") (pinfunction "I_13") (pintype "input"))
      (node (ref "E30") (pin "3") (pinfunction "O_3") (pintype "output"))
      (node (ref "E40") (pin "12") (pinfunction "I0_12") (pintype "input"))
      (node (ref "E41") (pin "1") (pinfunction "I0_1") (pintype "input"))
      (node (ref "J") (pin "T1") (pinfunction "P_T1") (pintype "passive"))
    )
    (net (code "30") (name "BTP3_OK") (class "Default")
      (node (ref "E21") (pin "6") (pinfunction "O_6") (pintype "output"))
      (node (ref "E26") (pin "3") (pinfunction "I6_3") (pintype "input"))
      (node (ref "E44") (pin "5") (pinfunction "I3_5") (pintype "input"))
      (node (ref "E45") (pin "9") (pinfunction "I0_9") (pintype "input"))
      (node (ref "H") (pin "K1") (pinfunction "P_K1") (pintype "passive"))
    )
    (net (code "31") (name "BUSY_ERROR") (class "Default")
      (node (ref "E22") (pin "6") (pinfunction "A1_6") (pintype "input"))
      (node (ref "E30") (pin "9") (pinfunction "I0_9") (pintype "input"))
      (node (ref "E50") (pin "15") (pinfunction "QA_15") (pintype "output"))
      (node (ref "R12") (pin "1") (pinfunction "1_1") (pintype "passive"))
    )
    (net (code "32") (name "B_BRK_RQ") (class "Default")
      (node (ref "E38") (pin "9") (pinfunction "Q_9") (pintype "output"))
      (node (ref "H") (pin "B2") (pinfunction "P_B2") (pintype "passive"))
    )
    (net (code "33") (name "B_DATA01") (class "Default")
      (node (ref "E20") (pin "10") (pinfunction "I1_10") (pintype "input"))
      (node (ref "H") (pin "T2") (pinfunction "P_T2") (pintype "passive"))
    )
    (net (code "34") (name "B_DRIVE_STATUS_ER") (class "Default")
      (node (ref "E40") (pin "3") (pinfunction "O_3") (pintype "output"))
      (node (ref "E53") (pin "3") (pinfunction "I1_3") (pintype "input"))
    )
    (net (code "35") (name "B_IO_PAUSE") (class "Default")
      (node (ref "E34") (pin "3") (pinfunction "I1_3") (pintype "input"))
      (node (ref "E35") (pin "14") (pinfunction "O_14") (pintype "output"))
      (node (ref "E51") (pin "3") (pinfunction "I1_3") (pintype "input"))
    )
    (net (code "36") (name "CLR_ALL") (class "Default")
      (node (ref "E19") (pin "8") (pinfunction "I0_8") (pintype "input"))
      (node (ref "E26") (pin "10") (pinfunction "I7_10") (pintype "input"))
      (node (ref "E26") (pin "9") (pinfunction "I8_9") (pintype "input"))
      (node (ref "E33") (pin "4") (pinfunction "I0_4") (pintype "input"))
      (node (ref "E33") (pin "5") (pinfunction "I1_5") (pintype "input"))
      (node (ref "E33") (pin "8") (pinfunction "O_8") (pintype "output"))
      (node (ref "E34") (pin "11") (pinfunction "I0_11") (pintype "input"))
      (node (ref "E34") (pin "5") (pinfunction "I0_5") (pintype "input"))
      (node (ref "H") (pin "D1") (pinfunction "P_D1") (pintype "passive"))
    )
    (net (code "37") (name "CRC_ERROR") (class "Default")
      (node (ref "E30") (pin "10") (pinfunction "I1_10") (pintype "input"))
      (node (ref "E49") (pin "1") (pinfunction "A0_1") (pintype "input"))
      (node (ref "E50") (pin "14") (pinfunction "QB_14") (pintype "output"))
      (node (ref "R13") (pin "1") (pinfunction "1_1") (pintype "passive"))
    )
    (net (code "38") (name "CYL_ADDRS_ER") (class "Default")
      (node (ref "E49") (pin "15") (pinfunction "A3_15") (pintype "input"))
      (node (ref "E50") (pin "10") (pinfunction "QE_10") (pintype "output"))
      (node (ref "E53") (pin "2") (pinfunction "I0_2") (pintype "input"))
    )
    (net (code "39") (name "DATA10") (class "Default")
      (node (ref "E44") (pin "1") (pinfunction "I0_1") (pintype "input"))
      (node (ref "J") (pin "A2") (pinfunction "P_A2") (pintype "passive"))
    )
    (net (code "40") (name "DATA_CLK_OK") (class "Default")
      (node (ref "E39") (pin "3") (pinfunction "CLK_3") (pintype "input"))
      (node (ref "H") (pin "C1") (pinfunction "P_C1") (pintype "passive"))
    )
    (net (code "41") (name "DATA_ENABLE") (class "Default")
      (node (ref "E20") (pin "4") (pinfunction "I0_4") (pintype "input"))
      (node (ref "H") (pin "N1") (pinfunction "P_N1") (pintype "passive"))
    )
    (net (code "42") (name "DATA_RQST_LATE") (class "Default")
      (node (ref "E39") (pin "5") (pinfunction "Q_5") (pintype "output"))
      (node (ref "E49") (pin "6") (pinfunction "A1_6") (pintype "input"))
    )
    (net (code "43") (name "DATA_STATE") (class "Default")
      (node (ref "E26") (pin "4") (pinfunction "I1_4") (pintype "input"))
      (node (ref "H") (pin "L1") (pinfunction "P_L1") (pintype "passive"))
    )
    (net (code "44") (name "DB4_ENA") (class "Default")
      (node (ref "E14") (pin "8") (pinfunction "CLR_8") (pintype "input"))
      (node (ref "E26") (pin "8") (pinfunction "O_8") (pintype "output"))
      (node (ref "E6") (pin "2") (pinfunction "I5_2") (pintype "input"))
    )
    (net (code "45") (name "DB_CLK") (class "Default")
      (node (ref "E11") (pin "10") (pinfunction "I1_10") (pintype "input"))
      (node (ref "E12") (pin "5") (pinfunction "CLK_5") (pintype "input"))
      (node (ref "E14") (pin "1") (pinfunction "CLK_1") (pintype "input"))
      (node (ref "E14") (pin "6") (pinfunction "CLK_6") (pintype "input"))
      (node (ref "E7") (pin "10") (pinfunction "B_10") (pintype "input"))
      (node (ref "E7") (pin "13") (pinfunction "Q_13") (pintype "output"))
    )
    (net (code "46") (name "DB_CONT1") (class "Default")
      (node (ref "E12") (pin "12") (pinfunction "Q_12") (pintype "output"))
      (node (ref "E46") (pin "5") (pinfunction "I1_5") (pintype "input"))
    )
    (net (code "47") (name "DB_CONT2") (class "Default")
      (node (ref "E11") (pin "5") (pinfunction "I1_5") (pintype "input"))
      (node (ref "E12") (pin "9") (pinfunction "Q_9") (pintype "output"))
      (node (ref "E25") (pin "9") (pinfunction "CLK_9") (pintype "input"))
      (node (ref "E4") (pin "9") (pinfunction "CLK_9") (pintype "input"))
      (node (ref "R14") (pin "1") (pinfunction "1_1") (pintype "passive"))
    )
    (net (code "48") (name "DB_CONT3") (class "Default")
      (node (ref "E10") (pin "9") (pinfunction "CLK_9") (pintype "input"))
      (node (ref "E13") (pin "8") (pinfunction "I0_8") (pintype "input"))
      (node (ref "E14") (pin "15") (pinfunction "Q_15") (pintype "output"))
      (node (ref "E18") (pin "9") (pinfunction "CLK_9") (pintype "input"))
      (node (ref "E28") (pin "8") (pinfunction "I0_8") (pintype "input"))
    )
    (net (code "49") (name "DB_CONT4") (class "Default")
      (node (ref "E13") (pin "12") (pinfunction "I1_12") (pintype "input"))
      (node (ref "E14") (pin "11") (pinfunction "Q_11") (pintype "output"))
      (node (ref "E52") (pin "10") (pinfunction "PRE_10") (pintype "input"))
      (node (ref "H") (pin "E2") (pinfunction "P_E2") (pintype "passive"))
    )
    (net (code "50") (name "DEVICE_RK") (class "Default")
      (node (ref "E1") (pin "3") (pinfunction "O_3") (pintype "output"))
      (node (ref "E31") (pin "3") (pinfunction "I_3") (pintype "input"))
      (node (ref "E36") (pin "8") (pinfunction "I0_8") (pintype "input"))
      (node (ref "E36") (pin "9") (pinfunction "I1_9") (pintype "input"))
      (node (ref "J") (pin "A1") (pinfunction "P_A1") (pintype "passive"))
    )
    (net (code "51") (name "DONE_FLAG") (class "Default")
      (node (ref "E39") (pin "8") (pinfunction "~{Q}_8") (pintype "output"))
      (node (ref "E8") (pin "1") (pinfunction "A0_1") (pintype "input"))
    )
    (net (code "52") (name "DRIVE_STATUS_BAD") (class "Default")
      (node (ref "E45") (pin "5") (pinfunction "I1_5") (pintype "input"))
      (node (ref "J") (pin "H2") (pinfunction "P_H2") (pintype "passive"))
    )
    (net (code "53") (name "DRIVE_STATUS_ER") (class "Default")
      (node (ref "E40") (pin "2") (pinfunction "I1_2") (pintype "input"))
      (node (ref "E49") (pin "10") (pinfunction "A2_10") (pintype "input"))
      (node (ref "E50") (pin "11") (pinfunction "QD_11") (pintype "output"))
    )
    (net (code "54") (name "DRV_REVO") (class "Default")
      (node (ref "E43") (pin "5") (pinfunction "UP_5") (pintype "input"))
      (node (ref "J") (pin "K2") (pinfunction "P_K2") (pintype "passive"))
    )
    (net (code "55") (name "DSK_WRT_STATUS") (class "Default")
      (node (ref "E51") (pin "12") (pinfunction "I1_12") (pintype "input"))
      (node (ref "J") (pin "D2") (pinfunction "P_D2") (pintype "passive"))
      (node (ref "R3") (pin "1") (pinfunction "1_1") (pintype "passive"))
      (node (ref "R4") (pin "2") (pinfunction "2_2") (pintype "passive"))
    )
    (net (code "56") (name "ENABLE_STATUS") (class "Default")
      (node (ref "E45") (pin "4") (pinfunction "I0_4") (pintype "input"))
      (node (ref "E54") (pin "6") (pinfunction "O_6") (pintype "output"))
    )
    (net (code "57") (name "ENAB_INT") (class "Default")
      (node (ref "E36") (pin "6") (pinfunction "I1_6") (pintype "input"))
      (node (ref "J") (pin "B1") (pinfunction "P_B1") (pintype "passive"))
    )
    (net (code "58") (name "ENAB_RK_DATA") (class "Default")
      (node (ref "E29") (pin "1") (pinfunction "A0_1") (pintype "input"))
      (node (ref "E31") (pin "5") (pinfunction "I_5") (pintype "input"))
      (node (ref "E33") (pin "11") (pinfunction "O_11") (pintype "output"))
    )
    (net (code "59") (name "ENAB_SEEK_DONE") (class "Default")
      (node (ref "E47") (pin "4") (pinfunction "I1_4") (pintype "input"))
      (node (ref "J") (pin "S1") (pinfunction "P_S1") (pintype "passive"))
    )
    (net (code "60") (name "GND") (class "Default")
      (node (ref "C1") (pin "2") (pinfunction "2_2") (pintype "passive"))
      (node (ref "C10") (pin "2") (pinfunction "2_2") (pintype "passive"))
      (node (ref "C11") (pin "2") (pinfunction "2_2") (pintype "passive"))
      (node (ref "C12") (pin "2") (pinfunction "2_2") (pintype "passive"))
      (node (ref "C13") (pin "2") (pinfunction "2_2") (pintype "passive"))
      (node (ref "C14") (pin "2") (pinfunction "2_2") (pintype "passive"))
      (node (ref "C15") (pin "2") (pinfunction "2_2") (pintype "passive"))
      (node (ref "C16") (pin "2") (pinfunction "2_2") (pintype "passive"))
      (node (ref "C17") (pin "2") (pinfunction "2_2") (pintype "passive"))
      (node (ref "C18") (pin "2") (pinfunction "2_2") (pintype "passive"))
      (node (ref "C19") (pin "2") (pinfunction "2_2") (pintype "passive"))
      (node (ref "C2") (pin "2") (pinfunction "2_2") (pintype "passive"))
      (node (ref "C20") (pin "2") (pinfunction "2_2") (pintype "passive"))
      (node (ref "C21") (pin "2") (pinfunction "2_2") (pintype "passive"))
      (node (ref "C22") (pin "2") (pinfunction "2_2") (pintype "passive"))
      (node (ref "C23") (pin "2") (pinfunction "2_2") (pintype "passive"))
      (node (ref "C24") (pin "2") (pinfunction "2_2") (pintype "passive"))
      (node (ref "C25") (pin "2") (pinfunction "2_2") (pintype "passive"))
      (node (ref "C26") (pin "2") (pinfunction "2_2") (pintype "passive"))
      (node (ref "C27") (pin "2") (pinfunction "2_2") (pintype "passive"))
      (node (ref "C28") (pin "2") (pinfunction "2_2") (pintype "passive"))
      (node (ref "C29") (pin "2") (pinfunction "2_2") (pintype "passive"))
      (node (ref "C3") (pin "2") (pinfunction "2_2") (pintype "passive"))
      (node (ref "C30") (pin "2") (pinfunction "2_2") (pintype "passive"))
      (node (ref "C31") (pin "2") (pinfunction "2_2") (pintype "passive"))
      (node (ref "C32") (pin "2") (pinfunction "2_2") (pintype "passive"))
      (node (ref "C33") (pin "2") (pinfunction "2_2") (pintype "passive"))
      (node (ref "C34") (pin "2") (pinfunction "2_2") (pintype "passive"))
      (node (ref "C35") (pin "2") (pinfunction "2_2") (pintype "passive"))
      (node (ref "C36") (pin "2") (pinfunction "2_2") (pintype "passive"))
      (node (ref "C37") (pin "2") (pinfunction "2_2") (pintype "passive"))
      (node (ref "C38") (pin "2") (pinfunction "2_2") (pintype "passive"))
      (node (ref "C39") (pin "2") (pinfunction "2_2") (pintype "passive"))
      (node (ref "C4") (pin "2") (pinfunction "2_2") (pintype "passive"))
      (node (ref "C40") (pin "2") (pinfunction "2_2") (pintype "passive"))
      (node (ref "C41") (pin "2") (pinfunction "2_2") (pintype "passive"))
      (node (ref "C42") (pin "2") (pinfunction "2_2") (pintype "passive"))
      (node (ref "C43") (pin "2") (pinfunction "2_2") (pintype "passive"))
      (node (ref "C44") (pin "2") (pinfunction "2_2") (pintype "passive"))
      (node (ref "C45") (pin "2") (pinfunction "2_2") (pintype "passive"))
      (node (ref "C46") (pin "2") (pinfunction "2_2") (pintype "passive"))
      (node (ref "C49") (pin "2") (pinfunction "2_2") (pintype "passive"))
      (node (ref "C5") (pin "2") (pinfunction "2_2") (pintype "passive"))
      (node (ref "C50") (pin "2") (pinfunction "2_2") (pintype "passive"))
      (node (ref "C51") (pin "2") (pinfunction "2_2") (pintype "passive"))
      (node (ref "C52") (pin "2") (pinfunction "2_2") (pintype "passive"))
      (node (ref "C53") (pin "-") (pinfunction "-_-") (pintype "passive"))
      (node (ref "C54") (pin "-") (pinfunction "-_-") (pintype "passive"))
      (node (ref "C55") (pin "-") (pinfunction "-_-") (pintype "passive"))
      (node (ref "C56") (pin "2") (pinfunction "2_2") (pintype "passive"))
      (node (ref "C6") (pin "2") (pinfunction "2_2") (pintype "passive"))
      (node (ref "C7") (pin "2") (pinfunction "2_2") (pintype "passive"))
      (node (ref "C8") (pin "2") (pinfunction "2_2") (pintype "passive"))
      (node (ref "C9") (pin "2") (pinfunction "2_2") (pintype "passive"))
      (node (ref "E12") (pin "3") (pinfunction "K_3") (pintype "input"))
      (node (ref "E15") (pin "11") (pinfunction "I0_11") (pintype "input"))
      (node (ref "E15") (pin "5") (pinfunction "I1_5") (pintype "input"))
      (node (ref "E26") (pin "1") (pinfunction "I4_1") (pintype "input"))
      (node (ref "E26") (pin "13") (pinfunction "I3_13") (pintype "input"))
      (node (ref "E29") (pin "7") (pinfunction "S1_7") (pintype "input"))
      (node (ref "E29") (pin "9") (pinfunction "S0_9") (pintype "input"))
      (node (ref "E30") (pin "5") (pinfunction "I1_5") (pintype "input"))
      (node (ref "E30") (pin "6") (pinfunction "I0_6") (pintype "input"))
      (node (ref "E33") (pin "1") (pinfunction "I0_1") (pintype "input"))
      (node (ref "E33") (pin "2") (pinfunction "I1_2") (pintype "input"))
      (node (ref "E34") (pin "2") (pinfunction "I0_2") (pintype "input"))
      (node (ref "E35") (pin "11") (pinfunction "I0_11") (pintype "input"))
      (node (ref "E35") (pin "5") (pinfunction "I1_5") (pintype "input"))
      (node (ref "E39") (pin "12") (pinfunction "D_12") (pintype "input"))
      (node (ref "E42") (pin "6") (pinfunction "I0_6") (pintype "input"))
      (node (ref "E52") (pin "12") (pinfunction "D_12") (pintype "input"))
      (node (ref "E7") (pin "9") (pinfunction "A_9") (pintype "input"))
      (node (ref "E8") (pin "10") (pinfunction "A2_10") (pintype "input"))
      (node (ref "OMNIBUS") (pin "AC2") (pinfunction "1_AC2") (pintype "bidirectional"))
      (node (ref "OMNIBUS") (pin "AF1") (pinfunction "1_AF1") (pintype "bidirectional"))
      (node (ref "OMNIBUS") (pin "AF2") (pinfunction "1_AF2") (pintype "bidirectional"))
      (node (ref "OMNIBUS") (pin "AN1") (pinfunction "1_AN1") (pintype "bidirectional"))
      (node (ref "OMNIBUS") (pin "AN2") (pinfunction "1_AN2") (pintype "bidirectional"))
      (node (ref "OMNIBUS") (pin "AT1") (pinfunction "1_AT1") (pintype "bidirectional"))
      (node (ref "OMNIBUS") (pin "AT2") (pinfunction "1_AT2") (pintype "bidirectional"))
      (node (ref "OMNIBUS") (pin "BC1") (pinfunction "1_BC1") (pintype "bidirectional"))
      (node (ref "OMNIBUS") (pin "BC2") (pinfunction "1_BC2") (pintype "bidirectional"))
      (node (ref "OMNIBUS") (pin "BF1") (pinfunction "1_BF1") (pintype "bidirectional"))
      (node (ref "OMNIBUS") (pin "BF2") (pinfunction "1_BF2") (pintype "bidirectional"))
      (node (ref "OMNIBUS") (pin "BN1") (pinfunction "1_BN1") (pintype "bidirectional"))
      (node (ref "OMNIBUS") (pin "BN2") (pinfunction "1_BN2") (pintype "bidirectional"))
      (node (ref "OMNIBUS") (pin "BT1") (pinfunction "1_BT1") (pintype "bidirectional"))
      (node (ref "OMNIBUS") (pin "BT2") (pinfunction "1_BT2") (pintype "bidirectional"))
      (node (ref "OMNIBUS") (pin "CC1") (pinfunction "1_CC1") (pintype "bidirectional"))
      (node (ref "OMNIBUS") (pin "CC2") (pinfunction "1_CC2") (pintype "bidirectional"))
      (node (ref "OMNIBUS") (pin "CF1") (pinfunction "1_CF1") (pintype "bidirectional"))
      (node (ref "OMNIBUS") (pin "CF2") (pinfunction "1_CF2") (pintype "bidirectional"))
      (node (ref "OMNIBUS") (pin "CN1") (pinfunction "1_CN1") (pintype "bidirectional"))
      (node (ref "OMNIBUS") (pin "CN2") (pinfunction "1_CN2") (pintype "bidirectional"))
      (node (ref "OMNIBUS") (pin "CT1") (pinfunction "1_CT1") (pintype "bidirectional"))
      (node (ref "OMNIBUS") (pin "CT2") (pinfunction "1_CT2") (pintype "bidirectional"))
      (node (ref "OMNIBUS") (pin "DC1") (pinfunction "1_DC1") (pintype "bidirectional"))
      (node (ref "OMNIBUS") (pin "DC2") (pinfunction "1_DC2") (pintype "bidirectional"))
      (node (ref "OMNIBUS") (pin "DF1") (pinfunction "1_DF1") (pintype "bidirectional"))
      (node (ref "OMNIBUS") (pin "DF2") (pinfunction "1_DF2") (pintype "bidirectional"))
      (node (ref "OMNIBUS") (pin "DN1") (pinfunction "1_DN1") (pintype "bidirectional"))
      (node (ref "OMNIBUS") (pin "DN2") (pinfunction "1_DN2") (pintype "bidirectional"))
      (node (ref "OMNIBUS") (pin "DT1") (pinfunction "1_DT1") (pintype "bidirectional"))
      (node (ref "OMNIBUS") (pin "DT2") (pinfunction "1_DT2") (pintype "bidirectional"))
      (node (ref "R1") (pin "1") (pinfunction "1_1") (pintype "passive"))
      (node (ref "R4") (pin "1") (pinfunction "1_1") (pintype "passive"))
    )
    (net (code "61") (name "HI_DATA_IN") (class "Default")
      (node (ref "E3") (pin "1") (pinfunction "SER_1") (pintype "input"))
      (node (ref "J") (pin "R2") (pinfunction "P_R2") (pintype "passive"))
    )
    (net (code "62") (name "HI_RD_CLK") (class "Default")
      (node (ref "E27") (pin "11") (pinfunction "I_11") (pintype "input"))
      (node (ref "E46") (pin "4") (pinfunction "I0_4") (pintype "input"))
      (node (ref "J") (pin "M1") (pinfunction "P_M1") (pintype "passive"))
    )
    (net (code "63") (name "HI_WRT_CLK") (class "Default")
      (node (ref "E11") (pin "11") (pinfunction "O_11") (pintype "output"))
      (node (ref "E3") (pin "9") (pinfunction "CK1_9") (pintype "input"))
      (node (ref "E32") (pin "9") (pinfunction "CK1_9") (pintype "input"))
      (node (ref "E5") (pin "9") (pinfunction "CK1_9") (pintype "input"))
    )
    (net (code "64") (name "IDLE") (class "Default")
      (node (ref "E20") (pin "12") (pinfunction "I0_12") (pintype "input"))
      (node (ref "E27") (pin "1") (pinfunction "I_1") (pintype "input"))
      (node (ref "E40") (pin "4") (pinfunction "I0_4") (pintype "input"))
      (node (ref "E43") (pin "14") (pinfunction "CLR_14") (pintype "input"))
      (node (ref "E47") (pin "5") (pinfunction "I2_5") (pintype "input"))
      (node (ref "E48") (pin "2") (pinfunction "I1_2") (pintype "input"))
      (node (ref "J") (pin "L2") (pinfunction "P_L2") (pintype "passive"))
    )
    (net (code "65") (name "INITIALIZE") (class "Default")
      (node (ref "E35") (pin "7") (pinfunction "I1_7") (pintype "input"))
      (node (ref "OMNIBUS") (pin "CR1") (pinfunction "1_CR1") (pintype "bidirectional"))
    )
    (net (code "66") (name "LAST_WORD_PL") (class "Default")
      (node (ref "E46") (pin "10") (pinfunction "I1_10") (pintype "input"))
      (node (ref "J") (pin "N2") (pinfunction "P_N2") (pintype "passive"))
    )
    (net (code "67") (name "LD_CMD_REG") (class "Default")
      (node (ref "E34") (pin "6") (pinfunction "I1_6") (pintype "input"))
      (node (ref "J") (pin "P1") (pinfunction "P_P1") (pintype "passive"))
    )
    (net (code "68") (name "LD_DB4") (class "Default")
      (node (ref "E11") (pin "8") (pinfunction "O_8") (pintype "output"))
      (node (ref "E17") (pin "8") (pinfunction "CK2_8") (pintype "input"))
      (node (ref "E24") (pin "8") (pinfunction "CK2_8") (pintype "input"))
      (node (ref "E9") (pin "8") (pinfunction "CK2_8") (pintype "input"))
    )
    (net (code "69") (name "LD_DB_AC") (class "Default")
      (node (ref "E21") (pin "8") (pinfunction "O_8") (pintype "output"))
      (node (ref "E26") (pin "2") (pinfunction "I5_2") (pintype "input"))
    )
    (net (code "70") (name "LD_DISK_ADDRS") (class "Default")
      (node (ref "E27") (pin "9") (pinfunction "I_9") (pintype "input"))
      (node (ref "E52") (pin "3") (pinfunction "CLK_3") (pintype "input"))
      (node (ref "J") (pin "B2") (pinfunction "P_B2") (pintype "passive"))
    )
    (net (code "71") (name "LD_RD_BUFFER") (class "Default")
      (node (ref "E13") (pin "2") (pinfunction "I0_2") (pintype "input"))
      (node (ref "E19") (pin "13") (pinfunction "O_13") (pintype "output"))
      (node (ref "E3") (pin "8") (pinfunction "CK2_8") (pintype "input"))
      (node (ref "E32") (pin "8") (pinfunction "CK2_8") (pintype "input"))
      (node (ref "E5") (pin "8") (pinfunction "CK2_8") (pintype "input"))
    )
    (net (code "72") (name "LO_MAIN_DATA") (class "Default")
      (node (ref "E9") (pin "1") (pinfunction "SER_1") (pintype "input"))
      (node (ref "H") (pin "V2") (pinfunction "P_V2") (pintype "passive"))
    )
    (net (code "73") (name "MAIN") (class "Default")
      (node (ref "E38") (pin "1") (pinfunction "CLR_1") (pintype "input"))
      (node (ref "E46") (pin "9") (pinfunction "I0_9") (pintype "input"))
      (node (ref "H") (pin "A2") (pinfunction "P_A2") (pintype "passive"))
    )
    (net (code "74") (name "MAIN_PL") (class "Default")
      (node (ref "E20") (pin "9") (pinfunction "I0_9") (pintype "input"))
      (node (ref "H") (pin "T1") (pinfunction "P_T1") (pintype "passive"))
    )
    (net (code "75") (name "MD_RD_BUFF") (class "Default")
      (node (ref "E27") (pin "4") (pinfunction "O_4") (pintype "output"))
      (node (ref "E3") (pin "6") (pinfunction "MOD_6") (pintype "input"))
      (node (ref "E32") (pin "6") (pinfunction "MOD_6") (pintype "input"))
      (node (ref "E5") (pin "6") (pinfunction "MOD_6") (pintype "input"))
      (node (ref "E51") (pin "2") (pinfunction "I0_2") (pintype "input"))
    )
    (net (code "76") (name "Net-(E1A-I0)") (class "Default")
      (node (ref "E1") (pin "4") (pinfunction "I0_4") (pintype "input"))
      (node (ref "W1W4") (pin "2") (pinfunction "2_2") (pintype "passive"))
    )
    (net (code "77") (name "Net-(E1A-I1)") (class "Default")
      (node (ref "E1") (pin "5") (pinfunction "I1_5") (pintype "input"))
      (node (ref "W2W5") (pin "2") (pinfunction "2_2") (pintype "passive"))
    )
    (net (code "78") (name "Net-(E1A-I2)") (class "Default")
      (node (ref "E1") (pin "6") (pinfunction "I2_6") (pintype "input"))
      (node (ref "W3W6") (pin "2") (pinfunction "2_2") (pintype "passive"))
    )
    (net (code "79") (name "Net-(E3A-QA)") (class "Default")
      (node (ref "E3") (pin "13") (pinfunction "QA_13") (pintype "output"))
      (node (ref "E4") (pin "3") (pinfunction "D1_3") (pintype "input"))
    )
    (net (code "80") (name "Net-(E3A-QB)") (class "Default")
      (node (ref "E3") (pin "12") (pinfunction "QB_12") (pintype "output"))
      (node (ref "E4") (pin "4") (pinfunction "D2_4") (pintype "input"))
    )
    (net (code "81") (name "Net-(E3A-QC)") (class "Default")
      (node (ref "E3") (pin "11") (pinfunction "QC_11") (pintype "output"))
      (node (ref "E4") (pin "6") (pinfunction "D3_6") (pintype "input"))
    )
    (net (code "82") (name "Net-(E3A-QD)") (class "Default")
      (node (ref "E3") (pin "10") (pinfunction "QD_10") (pintype "output"))
      (node (ref "E4") (pin "11") (pinfunction "D4_11") (pintype "input"))
      (node (ref "E5") (pin "1") (pinfunction "SER_1") (pintype "input"))
    )
    (net (code "83") (name "Net-(E4A-D5)") (class "Default")
      (node (ref "E4") (pin "13") (pinfunction "D5_13") (pintype "input"))
      (node (ref "E5") (pin "13") (pinfunction "QA_13") (pintype "output"))
    )
    (net (code "84") (name "Net-(E4A-D6)") (class "Default")
      (node (ref "E4") (pin "14") (pinfunction "D6_14") (pintype "input"))
      (node (ref "E5") (pin "12") (pinfunction "QB_12") (pintype "output"))
    )
    (net (code "85") (name "Net-(E6A-O)") (class "Default")
      (node (ref "E6") (pin "8") (pinfunction "O_8") (pintype "output"))
      (node (ref "E7") (pin "1") (pinfunction "A_1") (pintype "input"))
    )
    (net (code "86") (name "Net-(E7A-C)") (class "Default")
      (node (ref "C48") (pin "2") (pinfunction "2_2") (pintype "passive"))
      (node (ref "E7") (pin "14") (pinfunction "C_14") (pintype "input"))
    )
    (net (code "87") (name "Net-(E7A-R{slash}C)") (class "Default")
      (node (ref "C48") (pin "1") (pinfunction "1_1") (pintype "passive"))
      (node (ref "E7") (pin "15") (pinfunction "R/C_15") (pintype "input"))
      (node (ref "R7") (pin "1") (pinfunction "1_1") (pintype "passive"))
    )
    (net (code "88") (name "Net-(E7B-C)") (class "Default")
      (node (ref "C47") (pin "2") (pinfunction "2_2") (pintype "passive"))
      (node (ref "E7") (pin "6") (pinfunction "C_6") (pintype "input"))
    )
    (net (code "89") (name "Net-(E7B-R{slash}C)") (class "Default")
      (node (ref "C47") (pin "1") (pinfunction "1_1") (pintype "passive"))
      (node (ref "E7") (pin "7") (pinfunction "R/C_7") (pintype "input"))
      (node (ref "R6") (pin "1") (pinfunction "1_1") (pintype "passive"))
    )
    (net (code "90") (name "Net-(E10A-D1)") (class "Default")
      (node (ref "E10") (pin "3") (pinfunction "D1_3") (pintype "input"))
      (node (ref "E4") (pin "2") (pinfunction "Q1_2") (pintype "output"))
    )
    (net (code "91") (name "Net-(E10A-D2)") (class "Default")
      (node (ref "E10") (pin "4") (pinfunction "D2_4") (pintype "input"))
      (node (ref "E4") (pin "5") (pinfunction "Q2_5") (pintype "output"))
    )
    (net (code "92") (name "Net-(E10A-D3)") (class "Default")
      (node (ref "E10") (pin "6") (pinfunction "D3_6") (pintype "input"))
      (node (ref "E4") (pin "7") (pinfunction "Q3_7") (pintype "output"))
    )
    (net (code "93") (name "Net-(E10A-D4)") (class "Default")
      (node (ref "E10") (pin "11") (pinfunction "D4_11") (pintype "input"))
      (node (ref "E4") (pin "10") (pinfunction "Q4_10") (pintype "output"))
    )
    (net (code "94") (name "Net-(E10A-D5)") (class "Default")
      (node (ref "E10") (pin "13") (pinfunction "D5_13") (pintype "input"))
      (node (ref "E4") (pin "12") (pinfunction "Q5_12") (pintype "output"))
    )
    (net (code "95") (name "Net-(E10A-D6)") (class "Default")
      (node (ref "E10") (pin "14") (pinfunction "D6_14") (pintype "input"))
      (node (ref "E4") (pin "15") (pinfunction "Q6_15") (pintype "output"))
    )
    (net (code "96") (name "Net-(E10A-Q1)") (class "Default")
      (node (ref "E10") (pin "2") (pinfunction "Q1_2") (pintype "output"))
      (node (ref "E9") (pin "2") (pinfunction "A_2") (pintype "input"))
    )
    (net (code "97") (name "Net-(E10A-Q2)") (class "Default")
      (node (ref "E10") (pin "5") (pinfunction "Q2_5") (pintype "output"))
      (node (ref "E9") (pin "3") (pinfunction "B_3") (pintype "input"))
    )
    (net (code "98") (name "Net-(E10A-Q3)") (class "Default")
      (node (ref "E10") (pin "7") (pinfunction "Q3_7") (pintype "output"))
      (node (ref "E9") (pin "4") (pinfunction "C_4") (pintype "input"))
    )
    (net (code "99") (name "Net-(E10A-Q4)") (class "Default")
      (node (ref "E10") (pin "10") (pinfunction "Q4_10") (pintype "output"))
      (node (ref "E9") (pin "5") (pinfunction "D_5") (pintype "input"))
    )
    (net (code "100") (name "Net-(E10A-Q5)") (class "Default")
      (node (ref "E10") (pin "12") (pinfunction "Q5_12") (pintype "output"))
      (node (ref "E17") (pin "2") (pinfunction "A_2") (pintype "input"))
    )
    (net (code "101") (name "Net-(E10A-Q6)") (class "Default")
      (node (ref "E10") (pin "15") (pinfunction "Q6_15") (pintype "output"))
      (node (ref "E17") (pin "3") (pinfunction "B_3") (pintype "input"))
    )
    (net (code "102") (name "Net-(E11A-O)") (class "Default")
      (node (ref "E11") (pin "3") (pinfunction "O_3") (pintype "output"))
      (node (ref "E13") (pin "3") (pinfunction "I1_3") (pintype "input"))
    )
    (net (code "103") (name "Net-(E11B-O)") (class "Default")
      (node (ref "E11") (pin "6") (pinfunction "O_6") (pintype "output"))
      (node (ref "E19") (pin "9") (pinfunction "I1_9") (pintype "input"))
    )
    (net (code "104") (name "Net-(E12A-CL)") (class "Default")
      (node (ref "E12") (pin "2") (pinfunction "CL_2") (pintype "input"))
      (node (ref "E19") (pin "10") (pinfunction "O_10") (pintype "output"))
    )
    (net (code "105") (name "Net-(E12A-CLK)") (class "Default")
      (node (ref "E12") (pin "1") (pinfunction "CLK_1") (pintype "input"))
      (node (ref "E27") (pin "6") (pinfunction "O_6") (pintype "output"))
    )
    (net (code "106") (name "Net-(E12A-J)") (class "Default")
      (node (ref "E12") (pin "14") (pinfunction "J_14") (pintype "input"))
      (node (ref "E47") (pin "12") (pinfunction "O_12") (pintype "output"))
    )
    (net (code "107") (name "Net-(E13A-O)") (class "Default")
      (node (ref "E13") (pin "1") (pinfunction "O_1") (pintype "output"))
      (node (ref "E27") (pin "5") (pinfunction "I_5") (pintype "input"))
    )
    (net (code "108") (name "Net-(E13B-I0)") (class "Default")
      (node (ref "C49") (pin "1") (pinfunction "1_1") (pintype "passive"))
      (node (ref "E13") (pin "5") (pinfunction "I0_5") (pintype "input"))
      (node (ref "R14") (pin "2") (pinfunction "2_2") (pintype "passive"))
    )
    (net (code "109") (name "Net-(E14B-PRE)") (class "Default")
      (node (ref "E14") (pin "7") (pinfunction "PRE_7") (pintype "input"))
      (node (ref "E20") (pin "8") (pinfunction "O_8") (pintype "output"))
    )
    (net (code "110") (name "Net-(E14B-~{Q})") (class "Default")
      (node (ref "E14") (pin "10") (pinfunction "~{Q}_10") (pintype "output"))
      (node (ref "R15") (pin "1") (pinfunction "1_1") (pintype "passive"))
    )
    (net (code "111") (name "Net-(E17A-C)") (class "Default")
      (node (ref "E17") (pin "4") (pinfunction "C_4") (pintype "input"))
      (node (ref "E18") (pin "2") (pinfunction "Q1_2") (pintype "output"))
    )
    (net (code "112") (name "Net-(E17A-D)") (class "Default")
      (node (ref "E17") (pin "5") (pinfunction "D_5") (pintype "input"))
      (node (ref "E18") (pin "5") (pinfunction "Q2_5") (pintype "output"))
    )
    (net (code "113") (name "Net-(E18A-D1)") (class "Default")
      (node (ref "E18") (pin "3") (pinfunction "D1_3") (pintype "input"))
      (node (ref "E25") (pin "2") (pinfunction "Q1_2") (pintype "output"))
    )
    (net (code "114") (name "Net-(E18A-D2)") (class "Default")
      (node (ref "E18") (pin "4") (pinfunction "D2_4") (pintype "input"))
      (node (ref "E25") (pin "5") (pinfunction "Q2_5") (pintype "output"))
    )
    (net (code "115") (name "Net-(E18A-D3)") (class "Default")
      (node (ref "E18") (pin "6") (pinfunction "D3_6") (pintype "input"))
      (node (ref "E25") (pin "7") (pinfunction "Q3_7") (pintype "output"))
    )
    (net (code "116") (name "Net-(E18A-D4)") (class "Default")
      (node (ref "E18") (pin "11") (pinfunction "D4_11") (pintype "input"))
      (node (ref "E25") (pin "10") (pinfunction "Q4_10") (pintype "output"))
    )
    (net (code "117") (name "Net-(E18A-D5)") (class "Default")
      (node (ref "E18") (pin "13") (pinfunction "D5_13") (pintype "input"))
      (node (ref "E25") (pin "12") (pinfunction "Q5_12") (pintype "output"))
    )
    (net (code "118") (name "Net-(E18A-D6)") (class "Default")
      (node (ref "E18") (pin "14") (pinfunction "D6_14") (pintype "input"))
      (node (ref "E25") (pin "15") (pinfunction "Q6_15") (pintype "output"))
    )
    (net (code "119") (name "Net-(E18A-Q3)") (class "Default")
      (node (ref "E18") (pin "7") (pinfunction "Q3_7") (pintype "output"))
      (node (ref "E24") (pin "2") (pinfunction "A_2") (pintype "input"))
    )
    (net (code "120") (name "Net-(E18A-Q4)") (class "Default")
      (node (ref "E18") (pin "10") (pinfunction "Q4_10") (pintype "output"))
      (node (ref "E24") (pin "3") (pinfunction "B_3") (pintype "input"))
    )
    (net (code "121") (name "Net-(E18A-Q5)") (class "Default")
      (node (ref "E18") (pin "12") (pinfunction "Q5_12") (pintype "output"))
      (node (ref "E24") (pin "4") (pinfunction "C_4") (pintype "input"))
    )
    (net (code "122") (name "Net-(E18A-Q6)") (class "Default")
      (node (ref "E18") (pin "15") (pinfunction "Q6_15") (pintype "output"))
      (node (ref "E24") (pin "5") (pinfunction "D_5") (pintype "input"))
    )
    (net (code "123") (name "Net-(E25A-D1)") (class "Default")
      (node (ref "E25") (pin "3") (pinfunction "D1_3") (pintype "input"))
      (node (ref "E5") (pin "11") (pinfunction "QC_11") (pintype "output"))
    )
    (net (code "124") (name "Net-(E25A-D2)") (class "Default")
      (node (ref "E25") (pin "4") (pinfunction "D2_4") (pintype "input"))
      (node (ref "E32") (pin "1") (pinfunction "SER_1") (pintype "input"))
      (node (ref "E5") (pin "10") (pinfunction "QD_10") (pintype "output"))
    )
    (net (code "125") (name "Net-(E25A-D3)") (class "Default")
      (node (ref "E25") (pin "6") (pinfunction "D3_6") (pintype "input"))
      (node (ref "E32") (pin "13") (pinfunction "QA_13") (pintype "output"))
    )
    (net (code "126") (name "Net-(E25A-D4)") (class "Default")
      (node (ref "E25") (pin "11") (pinfunction "D4_11") (pintype "input"))
      (node (ref "E32") (pin "12") (pinfunction "QB_12") (pintype "output"))
    )
    (net (code "127") (name "Net-(E25A-D5)") (class "Default")
      (node (ref "E25") (pin "13") (pinfunction "D5_13") (pintype "input"))
      (node (ref "E32") (pin "11") (pinfunction "QC_11") (pintype "output"))
    )
    (net (code "128") (name "Net-(E25A-D6)") (class "Default")
      (node (ref "E25") (pin "14") (pinfunction "D6_14") (pintype "input"))
      (node (ref "E32") (pin "10") (pinfunction "QD_10") (pintype "output"))
    )
    (net (code "129") (name "Net-(E27A-O)") (class "Default")
      (node (ref "E27") (pin "2") (pinfunction "O_2") (pintype "output"))
      (node (ref "R10") (pin "1") (pinfunction "1_1") (pintype "passive"))
    )
    (net (code "130") (name "Net-(E27D-O)") (class "Default")
      (node (ref "E27") (pin "8") (pinfunction "O_8") (pintype "output"))
      (node (ref "E54") (pin "5") (pinfunction "I1_5") (pintype "input"))
    )
    (net (code "131") (name "Net-(E27F-O)") (class "Default")
      (node (ref "E27") (pin "12") (pinfunction "O_12") (pintype "output"))
      (node (ref "R8") (pin "1") (pinfunction "1_1") (pintype "passive"))
    )
    (net (code "132") (name "Net-(E28A-O)") (class "Default")
      (node (ref "E28") (pin "1") (pinfunction "O_1") (pintype "output"))
      (node (ref "E28") (pin "5") (pinfunction "I0_5") (pintype "input"))
    )
    (net (code "133") (name "Net-(E28B-I1)") (class "Default")
      (node (ref "E28") (pin "10") (pinfunction "O_10") (pintype "output"))
      (node (ref "E28") (pin "6") (pinfunction "I1_6") (pintype "input"))
    )
    (net (code "134") (name "Net-(E28B-O)") (class "Default")
      (node (ref "E28") (pin "11") (pinfunction "I0_11") (pintype "input"))
      (node (ref "E28") (pin "4") (pinfunction "O_4") (pintype "output"))
    )
    (net (code "135") (name "Net-(E28D-O)") (class "Default")
      (node (ref "E28") (pin "13") (pinfunction "O_13") (pintype "output"))
      (node (ref "E34") (pin "12") (pinfunction "I1_12") (pintype "input"))
    )
    (net (code "136") (name "Net-(E29A-A1)") (class "Default")
      (node (ref "E29") (pin "6") (pinfunction "A1_6") (pintype "input"))
      (node (ref "E44") (pin "8") (pinfunction "O_8") (pintype "output"))
    )
    (net (code "137") (name "Net-(E29A-B1)") (class "Default")
      (node (ref "E29") (pin "5") (pinfunction "B1_5") (pintype "input"))
      (node (ref "E40") (pin "8") (pinfunction "O_8") (pintype "output"))
    )
    (net (code "138") (name "Net-(E30C-O)") (class "Default")
      (node (ref "E30") (pin "14") (pinfunction "O_14") (pintype "output"))
      (node (ref "E48") (pin "1") (pinfunction "I0_1") (pintype "input"))
      (node (ref "E53") (pin "9") (pinfunction "I1_9") (pintype "input"))
    )
    (net (code "139") (name "Net-(E33C-I0)") (class "Default")
      (node (ref "E33") (pin "9") (pinfunction "I0_9") (pintype "input"))
      (node (ref "E35") (pin "2") (pinfunction "O_2") (pintype "output"))
    )
    (net (code "140") (name "Net-(E33C-I1)") (class "Default")
      (node (ref "E33") (pin "10") (pinfunction "I1_10") (pintype "input"))
      (node (ref "E41") (pin "6") (pinfunction "O_6") (pintype "output"))
    )
    (net (code "141") (name "Net-(E34B-O)") (class "Default")
      (node (ref "E34") (pin "4") (pinfunction "O_4") (pintype "output"))
      (node (ref "E48") (pin "4") (pinfunction "I0_4") (pintype "input"))
    )
    (net (code "142") (name "Net-(E34D-O)") (class "Default")
      (node (ref "E34") (pin "13") (pinfunction "O_13") (pintype "output"))
      (node (ref "E38") (pin "13") (pinfunction "CLR_13") (pintype "input"))
    )
    (net (code "143") (name "Net-(E35A-O)") (class "Default")
      (node (ref "E35") (pin "3") (pinfunction "O_3") (pintype "output"))
      (node (ref "E35") (pin "6") (pinfunction "I0_6") (pintype "input"))
    )
    (net (code "144") (name "Net-(E35D-O)") (class "Default")
      (node (ref "E35") (pin "13") (pinfunction "O_13") (pintype "output"))
      (node (ref "E38") (pin "2") (pinfunction "D_2") (pintype "input"))
    )
    (net (code "145") (name "Net-(E36A-I0)") (class "Default")
      (node (ref "E36") (pin "2") (pinfunction "I0_2") (pintype "input"))
      (node (ref "E36") (pin "5") (pinfunction "I0_5") (pintype "input"))
      (node (ref "E54") (pin "3") (pinfunction "O_3") (pintype "output"))
    )
    (net (code "146") (name "Net-(E39A-PRE)") (class "Default")
      (node (ref "E39") (pin "4") (pinfunction "PRE_4") (pintype "input"))
      (node (ref "E46") (pin "6") (pinfunction "O_6") (pintype "output"))
    )
    (net (code "147") (name "Net-(E39B-CLK)") (class "Default")
      (node (ref "E39") (pin "11") (pinfunction "CLK_11") (pintype "input"))
      (node (ref "E46") (pin "11") (pinfunction "O_11") (pintype "output"))
    )
    (net (code "148") (name "Net-(E39B-CLR)") (class "Default")
      (node (ref "E39") (pin "13") (pinfunction "CLR_13") (pintype "input"))
      (node (ref "E46") (pin "8") (pinfunction "O_8") (pintype "output"))
    )
    (net (code "149") (name "Net-(E40B-I1)") (class "Default")
      (node (ref "DL1") (pin "OUT") (pinfunction "OUT_OUT") (pintype "bidirectional"))
      (node (ref "E40") (pin "5") (pinfunction "I1_5") (pintype "input"))
      (node (ref "R16") (pin "1") (pinfunction "1_1") (pintype "passive"))
    )
    (net (code "150") (name "Net-(E40B-O)") (class "Default")
      (node (ref "E40") (pin "6") (pinfunction "O_6") (pintype "output"))
      (node (ref "E46") (pin "2") (pinfunction "I1_2") (pintype "input"))
    )
    (net (code "151") (name "Net-(E40D-I1)") (class "Default")
      (node (ref "C50") (pin "1") (pinfunction "1_1") (pintype "passive"))
      (node (ref "E40") (pin "13") (pinfunction "I1_13") (pintype "input"))
      (node (ref "R8") (pin "2") (pinfunction "2_2") (pintype "passive"))
    )
    (net (code "152") (name "Net-(E41D-I3)") (class "Default")
      (node (ref "E41") (pin "13") (pinfunction "I3_13") (pintype "input"))
      (node (ref "E45") (pin "3") (pinfunction "O_3") (pintype "output"))
    )
    (net (code "153") (name "Net-(E41D-O)") (class "Default")
      (node (ref "E41") (pin "8") (pinfunction "O_8") (pintype "output"))
      (node (ref "E48") (pin "12") (pinfunction "I0_12") (pintype "input"))
    )
    (net (code "154") (name "Net-(E45B-O)") (class "Default")
      (node (ref "E45") (pin "6") (pinfunction "O_6") (pintype "output"))
      (node (ref "R5") (pin "1") (pinfunction "1_1") (pintype "passive"))
    )
    (net (code "155") (name "Net-(E45C-O)") (class "Default")
      (node (ref "E45") (pin "8") (pinfunction "O_8") (pintype "output"))
      (node (ref "E48") (pin "5") (pinfunction "I1_5") (pintype "input"))
    )
    (net (code "156") (name "Net-(E45D-I1)") (class "Default")
      (node (ref "C52") (pin "1") (pinfunction "1_1") (pintype "passive"))
      (node (ref "E45") (pin "13") (pinfunction "I1_13") (pintype "input"))
      (node (ref "R5") (pin "2") (pinfunction "2_2") (pintype "passive"))
    )
    (net (code "157") (name "Net-(E46A-I0)") (class "Default")
      (node (ref "C51") (pin "1") (pinfunction "1_1") (pintype "passive"))
      (node (ref "E46") (pin "1") (pinfunction "I0_1") (pintype "input"))
      (node (ref "R10") (pin "2") (pinfunction "2_2") (pintype "passive"))
    )
    (net (code "158") (name "Net-(E46D-I0)") (class "Default")
      (node (ref "E46") (pin "12") (pinfunction "I0_12") (pintype "input"))
      (node (ref "E47") (pin "6") (pinfunction "O_6") (pintype "output"))
    )
    (net (code "159") (name "Net-(E47C-I1)") (class "Default")
      (node (ref "E47") (pin "10") (pinfunction "I1_10") (pintype "input"))
      (node (ref "E53") (pin "1") (pinfunction "O_1") (pintype "output"))
    )
    (net (code "160") (name "Net-(E47C-I2)") (class "Default")
      (node (ref "E47") (pin "11") (pinfunction "I2_11") (pintype "input"))
      (node (ref "E53") (pin "4") (pinfunction "O_4") (pintype "output"))
    )
    (net (code "161") (name "Net-(E47C-O)") (class "Default")
      (node (ref "E47") (pin "8") (pinfunction "O_8") (pintype "output"))
      (node (ref "E53") (pin "11") (pinfunction "I0_11") (pintype "input"))
      (node (ref "E53") (pin "8") (pinfunction "I0_8") (pintype "input"))
    )
    (net (code "162") (name "Net-(E48A-O)") (class "Default")
      (node (ref "E48") (pin "3") (pinfunction "O_3") (pintype "output"))
      (node (ref "E53") (pin "12") (pinfunction "I1_12") (pintype "input"))
    )
    (net (code "163") (name "Net-(E48C-O)") (class "Default")
      (node (ref "E48") (pin "13") (pinfunction "I1_13") (pintype "input"))
      (node (ref "E48") (pin "8") (pinfunction "O_8") (pintype "output"))
    )
    (net (code "164") (name "Net-(E51D-O)") (class "Default")
      (node (ref "E51") (pin "13") (pinfunction "O_13") (pintype "output"))
      (node (ref "E52") (pin "2") (pinfunction "D_2") (pintype "input"))
    )
    (net (code "165") (name "Net-(E52B-CLK)") (class "Default")
      (node (ref "E52") (pin "11") (pinfunction "CLK_11") (pintype "input"))
      (node (ref "E54") (pin "8") (pinfunction "O_8") (pintype "output"))
    )
    (net (code "166") (name "POWER_OK") (class "Default")
      (node (ref "E35") (pin "4") (pinfunction "I0_4") (pintype "input"))
      (node (ref "OMNIBUS") (pin "BV2") (pinfunction "1_BV2") (pintype "bidirectional"))
    )
    (net (code "167") (name "RDY_S{slash}R{slash}W") (class "Default")
      (node (ref "E47") (pin "3") (pinfunction "I0_3") (pintype "input"))
      (node (ref "J") (pin "L1") (pinfunction "P_L1") (pintype "passive"))
    )
    (net (code "168") (name "RK_DATA0") (class "Default")
      (node (ref "E16") (pin "5") (pinfunction "I_5") (pintype "input"))
      (node (ref "E9") (pin "13") (pinfunction "QA_13") (pintype "output"))
    )
    (net (code "169") (name "RK_DATA1") (class "Default")
      (node (ref "E16") (pin "3") (pinfunction "I_3") (pintype "input"))
      (node (ref "E9") (pin "12") (pinfunction "QB_12") (pintype "output"))
    )
    (net (code "170") (name "RK_DATA2") (class "Default")
      (node (ref "E16") (pin "11") (pinfunction "I_11") (pintype "input"))
      (node (ref "E9") (pin "11") (pinfunction "QC_11") (pintype "output"))
    )
    (net (code "171") (name "RK_DATA3") (class "Default")
      (node (ref "E16") (pin "9") (pinfunction "I_9") (pintype "input"))
      (node (ref "E17") (pin "1") (pinfunction "SER_1") (pintype "input"))
      (node (ref "E9") (pin "10") (pinfunction "QD_10") (pintype "output"))
    )
    (net (code "172") (name "RK_DATA4") (class "Default")
      (node (ref "E17") (pin "13") (pinfunction "QA_13") (pintype "output"))
      (node (ref "E23") (pin "9") (pinfunction "I_9") (pintype "input"))
    )
    (net (code "173") (name "RK_DATA5") (class "Default")
      (node (ref "E16") (pin "13") (pinfunction "I_13") (pintype "input"))
      (node (ref "E17") (pin "12") (pinfunction "QB_12") (pintype "output"))
    )
    (net (code "174") (name "RK_DATA6") (class "Default")
      (node (ref "E16") (pin "1") (pinfunction "I_1") (pintype "input"))
      (node (ref "E17") (pin "11") (pinfunction "QC_11") (pintype "output"))
    )
    (net (code "175") (name "RK_DATA7") (class "Default")
      (node (ref "E17") (pin "10") (pinfunction "QD_10") (pintype "output"))
      (node (ref "E23") (pin "11") (pinfunction "I_11") (pintype "input"))
      (node (ref "E24") (pin "1") (pinfunction "SER_1") (pintype "input"))
    )
    (net (code "176") (name "RK_DATA8") (class "Default")
      (node (ref "E23") (pin "1") (pinfunction "I_1") (pintype "input"))
      (node (ref "E24") (pin "13") (pinfunction "QA_13") (pintype "output"))
    )
    (net (code "177") (name "RK_DATA9") (class "Default")
      (node (ref "E23") (pin "5") (pinfunction "I_5") (pintype "input"))
      (node (ref "E24") (pin "12") (pinfunction "QB_12") (pintype "output"))
    )
    (net (code "178") (name "RK_DATA10") (class "Default")
      (node (ref "E23") (pin "3") (pinfunction "I_3") (pintype "input"))
      (node (ref "E24") (pin "11") (pinfunction "QC_11") (pintype "output"))
    )
    (net (code "179") (name "RK_DATA11") (class "Default")
      (node (ref "E23") (pin "13") (pinfunction "I_13") (pintype "input"))
      (node (ref "E24") (pin "10") (pinfunction "QD_10") (pintype "output"))
      (node (ref "H") (pin "F1") (pinfunction "P_F1") (pintype "passive"))
    )
    (net (code "180") (name "SEEK_FAIL") (class "Default")
      (node (ref "E8") (pin "15") (pinfunction "A3_15") (pintype "input"))
      (node (ref "H") (pin "U2") (pinfunction "P_U2") (pintype "passive"))
    )
    (net (code "181") (name "SET_BUSY_ER") (class "Default")
      (node (ref "E48") (pin "11") (pinfunction "O_11") (pintype "output"))
      (node (ref "E50") (pin "2") (pinfunction "A_2") (pintype "input"))
    )
    (net (code "182") (name "SET_CRC_ER") (class "Default")
      (node (ref "E50") (pin "3") (pinfunction "B_3") (pintype "input"))
      (node (ref "E51") (pin "4") (pinfunction "O_4") (pintype "output"))
    )
    (net (code "183") (name "SET_CYL_ADDRS_ER") (class "Default")
      (node (ref "E50") (pin "7") (pinfunction "E_7") (pintype "input"))
      (node (ref "E51") (pin "10") (pinfunction "O_10") (pintype "output"))
    )
    (net (code "184") (name "SET_STATUS_ER") (class "Default")
      (node (ref "E45") (pin "11") (pinfunction "O_11") (pintype "output"))
      (node (ref "E50") (pin "6") (pinfunction "D_6") (pintype "input"))
    )
    (net (code "185") (name "SET_TIME_OUT_ER") (class "Default")
      (node (ref "E43") (pin "7") (pinfunction "QD_7") (pintype "output"))
      (node (ref "E50") (pin "4") (pinfunction "C_4") (pintype "input"))
    )
    (net (code "186") (name "SHORT_TP3") (class "Default")
      (node (ref "E40") (pin "11") (pinfunction "O_11") (pintype "output"))
      (node (ref "E48") (pin "9") (pinfunction "I0_9") (pintype "input"))
    )
    (net (code "187") (name "TEST_CLK") (class "Default")
      (node (ref "E34") (pin "8") (pinfunction "I0_8") (pintype "input"))
      (node (ref "E7") (pin "5") (pinfunction "Q_5") (pintype "output"))
    )
    (net (code "188") (name "TIME_OUT_ER") (class "Default")
      (node (ref "E22") (pin "10") (pinfunction "A2_10") (pintype "input"))
      (node (ref "E50") (pin "13") (pinfunction "QC_13") (pintype "output"))
      (node (ref "E53") (pin "6") (pinfunction "I1_6") (pintype "input"))
    )
    (net (code "189") (name "TP1") (class "Default")
      (node (ref "E30") (pin "11") (pinfunction "I0_11") (pintype "input"))
      (node (ref "E30") (pin "12") (pinfunction "I1_12") (pintype "input"))
      (node (ref "OMNIBUS") (pin "CD2") (pinfunction "1_CD2") (pintype "bidirectional"))
    )
    (net (code "190") (name "TP2") (class "Default")
      (node (ref "E30") (pin "7") (pinfunction "I1_7") (pintype "input"))
      (node (ref "OMNIBUS") (pin "CE2") (pinfunction "1_CE2") (pintype "bidirectional"))
    )
    (net (code "191") (name "TP3") (class "Default")
      (node (ref "E30") (pin "4") (pinfunction "I0_4") (pintype "input"))
      (node (ref "OMNIBUS") (pin "CH2") (pinfunction "1_CH2") (pintype "bidirectional"))
    )
    (net (code "192") (name "VCC") (class "Default")
      (node (ref "C1") (pin "1") (pinfunction "1_1") (pintype "passive"))
      (node (ref "C10") (pin "1") (pinfunction "1_1") (pintype "passive"))
      (node (ref "C11") (pin "1") (pinfunction "1_1") (pintype "passive"))
      (node (ref "C12") (pin "1") (pinfunction "1_1") (pintype "passive"))
      (node (ref "C13") (pin "1") (pinfunction "1_1") (pintype "passive"))
      (node (ref "C14") (pin "1") (pinfunction "1_1") (pintype "passive"))
      (node (ref "C15") (pin "1") (pinfunction "1_1") (pintype "passive"))
      (node (ref "C16") (pin "1") (pinfunction "1_1") (pintype "passive"))
      (node (ref "C17") (pin "1") (pinfunction "1_1") (pintype "passive"))
      (node (ref "C18") (pin "1") (pinfunction "1_1") (pintype "passive"))
      (node (ref "C19") (pin "1") (pinfunction "1_1") (pintype "passive"))
      (node (ref "C2") (pin "1") (pinfunction "1_1") (pintype "passive"))
      (node (ref "C20") (pin "1") (pinfunction "1_1") (pintype "passive"))
      (node (ref "C21") (pin "1") (pinfunction "1_1") (pintype "passive"))
      (node (ref "C22") (pin "1") (pinfunction "1_1") (pintype "passive"))
      (node (ref "C23") (pin "1") (pinfunction "1_1") (pintype "passive"))
      (node (ref "C24") (pin "1") (pinfunction "1_1") (pintype "passive"))
      (node (ref "C25") (pin "1") (pinfunction "1_1") (pintype "passive"))
      (node (ref "C26") (pin "1") (pinfunction "1_1") (pintype "passive"))
      (node (ref "C27") (pin "1") (pinfunction "1_1") (pintype "passive"))
      (node (ref "C28") (pin "1") (pinfunction "1_1") (pintype "passive"))
      (node (ref "C29") (pin "1") (pinfunction "1_1") (pintype "passive"))
      (node (ref "C3") (pin "1") (pinfunction "1_1") (pintype "passive"))
      (node (ref "C30") (pin "1") (pinfunction "1_1") (pintype "passive"))
      (node (ref "C31") (pin "1") (pinfunction "1_1") (pintype "passive"))
      (node (ref "C32") (pin "1") (pinfunction "1_1") (pintype "passive"))
      (node (ref "C33") (pin "1") (pinfunction "1_1") (pintype "passive"))
      (node (ref "C34") (pin "1") (pinfunction "1_1") (pintype "passive"))
      (node (ref "C35") (pin "1") (pinfunction "1_1") (pintype "passive"))
      (node (ref "C36") (pin "1") (pinfunction "1_1") (pintype "passive"))
      (node (ref "C37") (pin "1") (pinfunction "1_1") (pintype "passive"))
      (node (ref "C38") (pin "1") (pinfunction "1_1") (pintype "passive"))
      (node (ref "C39") (pin "1") (pinfunction "1_1") (pintype "passive"))
      (node (ref "C4") (pin "1") (pinfunction "1_1") (pintype "passive"))
      (node (ref "C40") (pin "1") (pinfunction "1_1") (pintype "passive"))
      (node (ref "C41") (pin "1") (pinfunction "1_1") (pintype "passive"))
      (node (ref "C42") (pin "1") (pinfunction "1_1") (pintype "passive"))
      (node (ref "C43") (pin "1") (pinfunction "1_1") (pintype "passive"))
      (node (ref "C44") (pin "1") (pinfunction "1_1") (pintype "passive"))
      (node (ref "C45") (pin "1") (pinfunction "1_1") (pintype "passive"))
      (node (ref "C46") (pin "1") (pinfunction "1_1") (pintype "passive"))
      (node (ref "C5") (pin "1") (pinfunction "1_1") (pintype "passive"))
      (node (ref "C53") (pin "+") (pinfunction "+_+") (pintype "passive"))
      (node (ref "C54") (pin "+") (pinfunction "+_+") (pintype "passive"))
      (node (ref "C55") (pin "+") (pinfunction "+_+") (pintype "passive"))
      (node (ref "C6") (pin "1") (pinfunction "1_1") (pintype "passive"))
      (node (ref "C7") (pin "1") (pinfunction "1_1") (pintype "passive"))
      (node (ref "C8") (pin "1") (pinfunction "1_1") (pintype "passive"))
      (node (ref "C9") (pin "1") (pinfunction "1_1") (pintype "passive"))
      (node (ref "DL1") (pin "GND@1") (pinfunction "GND_GND@1") (pintype "power_in"))
      (node (ref "DL1") (pin "GND@2") (pinfunction "GND_GND@2") (pintype "power_in"))
      (node (ref "OMNIBUS") (pin "AA2") (pinfunction "1_AA2") (pintype "bidirectional"))
      (node (ref "OMNIBUS") (pin "BA2") (pinfunction "1_BA2") (pintype "bidirectional"))
      (node (ref "OMNIBUS") (pin "CA2") (pinfunction "1_CA2") (pintype "bidirectional"))
      (node (ref "R11") (pin "2") (pinfunction "2_2") (pintype "passive"))
      (node (ref "R12") (pin "2") (pinfunction "2_2") (pintype "passive"))
      (node (ref "R13") (pin "2") (pinfunction "2_2") (pintype "passive"))
      (node (ref "R16") (pin "2") (pinfunction "2_2") (pintype "passive"))
      (node (ref "R17") (pin "2") (pinfunction "2_2") (pintype "passive"))
      (node (ref "R2") (pin "2") (pinfunction "2_2") (pintype "passive"))
      (node (ref "R3") (pin "2") (pinfunction "2_2") (pintype "passive"))
      (node (ref "R6") (pin "2") (pinfunction "2_2") (pintype "passive"))
      (node (ref "R7") (pin "2") (pinfunction "2_2") (pintype "passive"))
      (node (ref "R9") (pin "2") (pinfunction "2_2") (pintype "passive"))
    )
    (net (code "193") (name "WRITE") (class "Default")
      (node (ref "E26") (pin "5") (pinfunction "I11_5") (pintype "input"))
      (node (ref "H") (pin "M2") (pinfunction "P_M2") (pintype "passive"))
    )
    (net (code "194") (name "WRT_BUFF_SHFT") (class "Default")
      (node (ref "E20") (pin "3") (pinfunction "O_3") (pintype "output"))
      (node (ref "E31") (pin "9") (pinfunction "I_9") (pintype "input"))
    )
    (net (code "195") (name "WRT_BUF_DATA") (class "Default")
      (node (ref "E21") (pin "12") (pinfunction "O_12") (pintype "output"))
      (node (ref "E54") (pin "10") (pinfunction "I1_10") (pintype "input"))
    )
    (net (code "196") (name "WRT_LOCK_ER") (class "Default")
      (node (ref "E22") (pin "15") (pinfunction "A3_15") (pintype "input"))
      (node (ref "E52") (pin "5") (pinfunction "Q_5") (pintype "output"))
      (node (ref "E53") (pin "5") (pinfunction "I0_5") (pintype "input"))
    )
    (net (code "197") (name "unconnected-(E6A-I9-Pad12)") (class "Default")
      (node (ref "E6") (pin "12") (pinfunction "I9_12") (pintype "passive"))
    )
    (net (code "198") (name "unconnected-(E6A-I10-Pad11)") (class "Default")
      (node (ref "E6") (pin "11") (pinfunction "I10_11") (pintype "passive"))
    )
    (net (code "199") (name "unconnected-(E7A-~{Q}-Pad4)") (class "Default")
      (node (ref "E7") (pin "4") (pinfunction "~{Q}_4") (pintype "output"))
    )
    (net (code "200") (name "unconnected-(E26A-I9-Pad12)") (class "Default")
      (node (ref "E26") (pin "12") (pinfunction "I9_12") (pintype "passive"))
    )
    (net (code "201") (name "unconnected-(E26A-I10-Pad11)") (class "Default")
      (node (ref "E26") (pin "11") (pinfunction "I10_11") (pintype "passive"))
    )
    (net (code "202") (name "unconnected-(E29A-A2-Pad10)") (class "Default")
      (node (ref "E29") (pin "10") (pinfunction "A2_10") (pintype "input"))
    )
    (net (code "203") (name "unconnected-(E29A-A3-Pad15)") (class "Default")
      (node (ref "E29") (pin "15") (pinfunction "A3_15") (pintype "input"))
    )
    (net (code "204") (name "unconnected-(E29A-B2-Pad11)") (class "Default")
      (node (ref "E29") (pin "11") (pinfunction "B2_11") (pintype "input"))
    )
    (net (code "205") (name "unconnected-(E29A-B3-Pad14)") (class "Default")
      (node (ref "E29") (pin "14") (pinfunction "B3_14") (pintype "input"))
    )
    (net (code "206") (name "unconnected-(E29A-F2-Pad12)") (class "Default")
      (node (ref "E29") (pin "12") (pinfunction "F2_12") (pintype "open_collector"))
    )
    (net (code "207") (name "unconnected-(E29A-F3-Pad13)") (class "Default")
      (node (ref "E29") (pin "13") (pinfunction "F3_13") (pintype "open_collector"))
    )
    (net (code "208") (name "unconnected-(E37A-0-Pad13)") (class "Default")
      (node (ref "E37") (pin "13") (pinfunction "0_13") (pintype "output"))
    )
    (net (code "209") (name "unconnected-(E37A-8-Pad6)") (class "Default")
      (node (ref "E37") (pin "6") (pinfunction "8_6") (pintype "output"))
    )
    (net (code "210") (name "unconnected-(E37A-9-Pad7)") (class "Default")
      (node (ref "E37") (pin "7") (pinfunction "9_7") (pintype "output"))
    )
    (net (code "211") (name "unconnected-(E38B-~{Q}-Pad8)") (class "Default")
      (node (ref "E38") (pin "8") (pinfunction "~{Q}_8") (pintype "output"))
    )
    (net (code "212") (name "unconnected-(E43A-A-Pad15)") (class "Default")
      (node (ref "E43") (pin "15") (pinfunction "A_15") (pintype "input"))
    )
    (net (code "213") (name "unconnected-(E43A-B-Pad1)") (class "Default")
      (node (ref "E43") (pin "1") (pinfunction "B_1") (pintype "input"))
    )
    (net (code "214") (name "unconnected-(E43A-BO-Pad13)") (class "Default")
      (node (ref "E43") (pin "13") (pinfunction "BO_13") (pintype "output"))
    )
    (net (code "215") (name "unconnected-(E43A-C-Pad10)") (class "Default")
      (node (ref "E43") (pin "10") (pinfunction "C_10") (pintype "input"))
    )
    (net (code "216") (name "unconnected-(E43A-CO-Pad12)") (class "Default")
      (node (ref "E43") (pin "12") (pinfunction "CO_12") (pintype "output"))
    )
    (net (code "217") (name "unconnected-(E43A-D-Pad9)") (class "Default")
      (node (ref "E43") (pin "9") (pinfunction "D_9") (pintype "input"))
    )
    (net (code "218") (name "unconnected-(E43A-QA-Pad3)") (class "Default")
      (node (ref "E43") (pin "3") (pinfunction "QA_3") (pintype "output"))
    )
    (net (code "219") (name "unconnected-(E43A-QB-Pad2)") (class "Default")
      (node (ref "E43") (pin "2") (pinfunction "QB_2") (pintype "output"))
    )
    (net (code "220") (name "unconnected-(E43A-QC-Pad6)") (class "Default")
      (node (ref "E43") (pin "6") (pinfunction "QC_6") (pintype "output"))
    )
    (net (code "221") (name "unconnected-(E50A-SER-Pad9)") (class "Default")
      (node (ref "E50") (pin "9") (pinfunction "SER_9") (pintype "input"))
    )
    (net (code "222") (name "unconnected-(E52B-~{Q}-Pad8)") (class "Default")
      (node (ref "E52") (pin "8") (pinfunction "~{Q}_8") (pintype "output"))
    )
    (net (code "223") (name "~{6RK1}") (class "Default")
      (node (ref "E31") (pin "11") (pinfunction "I_11") (pintype "input"))
      (node (ref "E37") (pin "12") (pinfunction "1_12") (pintype "output"))
    )
    (net (code "224") (name "~{6RK2}") (class "Default")
      (node (ref "DL1") (pin "IN") (pinfunction "IN_IN") (pintype "bidirectional"))
      (node (ref "E31") (pin "13") (pinfunction "I_13") (pintype "input"))
      (node (ref "E37") (pin "11") (pinfunction "2_11") (pintype "output"))
      (node (ref "E44") (pin "12") (pinfunction "I2_12") (pintype "input"))
      (node (ref "R17") (pin "1") (pinfunction "1_1") (pintype "passive"))
    )
    (net (code "225") (name "~{6RK3_OK}") (class "Default")
      (node (ref "E21") (pin "10") (pinfunction "O_10") (pintype "output"))
      (node (ref "H") (pin "S2") (pinfunction "P_S2") (pintype "passive"))
    )
    (net (code "226") (name "~{6RK3}") (class "Default")
      (node (ref "E19") (pin "5") (pinfunction "I0_5") (pintype "input"))
      (node (ref "E37") (pin "10") (pinfunction "3_10") (pintype "output"))
      (node (ref "E40") (pin "9") (pinfunction "I0_9") (pintype "input"))
      (node (ref "E41") (pin "9") (pinfunction "I0_9") (pintype "input"))
    )
    (net (code "227") (name "~{6RK4}") (class "Default")
      (node (ref "E37") (pin "9") (pinfunction "4_9") (pintype "output"))
      (node (ref "E41") (pin "12") (pinfunction "I2_12") (pintype "input"))
      (node (ref "E44") (pin "13") (pinfunction "I3_13") (pintype "input"))
      (node (ref "J") (pin "S2") (pinfunction "P_S2") (pintype "passive"))
    )
    (net (code "228") (name "~{6RK5}") (class "Default")
      (node (ref "E22") (pin "7") (pinfunction "S1_7") (pintype "input"))
      (node (ref "E29") (pin "2") (pinfunction "B0_2") (pintype "input"))
      (node (ref "E37") (pin "3") (pinfunction "5_3") (pintype "output"))
      (node (ref "E44") (pin "10") (pinfunction "I1_10") (pintype "input"))
      (node (ref "E49") (pin "7") (pinfunction "S1_7") (pintype "input"))
      (node (ref "E8") (pin "7") (pinfunction "S1_7") (pintype "input"))
    )
    (net (code "229") (name "~{6RK6}") (class "Default")
      (node (ref "E21") (pin "1") (pinfunction "I_1") (pintype "input"))
      (node (ref "E37") (pin "4") (pinfunction "6_4") (pintype "output"))
      (node (ref "E41") (pin "10") (pinfunction "I1_10") (pintype "input"))
      (node (ref "E44") (pin "9") (pinfunction "I0_9") (pintype "input"))
    )
    (net (code "230") (name "~{6RK7}") (class "Default")
      (node (ref "E19") (pin "2") (pinfunction "I0_2") (pintype "input"))
      (node (ref "E31") (pin "1") (pinfunction "I_1") (pintype "input"))
      (node (ref "E37") (pin "5") (pinfunction "7_5") (pintype "output"))
    )
    (net (code "231") (name "~{AC7}") (class "Default")
      (node (ref "E38") (pin "6") (pinfunction "~{Q}_6") (pintype "output"))
      (node (ref "H") (pin "B1") (pinfunction "P_B1") (pintype "passive"))
    )
    (net (code "232") (name "~{BDATA10}") (class "Default")
      (node (ref "E41") (pin "2") (pinfunction "I1_2") (pintype "input"))
      (node (ref "J") (pin "P2") (pinfunction "P_P2") (pintype "passive"))
    )
    (net (code "233") (name "~{BDATA11}") (class "Default")
      (node (ref "E44") (pin "2") (pinfunction "I1_2") (pintype "input"))
      (node (ref "E45") (pin "2") (pinfunction "I1_2") (pintype "input"))
      (node (ref "J") (pin "H1") (pinfunction "P_H1") (pintype "passive"))
    )
    (net (code "234") (name "~{BRK_DIR}") (class "Default")
      (node (ref "E20") (pin "5") (pinfunction "I1_5") (pintype "input"))
      (node (ref "H") (pin "P2") (pinfunction "P_P2") (pintype "passive"))
    )
    (net (code "235") (name "~{BTP1}") (class "Default")
      (node (ref "E30") (pin "13") (pinfunction "O_13") (pintype "output"))
      (node (ref "E38") (pin "11") (pinfunction "CLK_11") (pintype "input"))
    )
    (net (code "236") (name "~{BTP3_OK}") (class "Default")
      (node (ref "E20") (pin "11") (pinfunction "O_11") (pintype "output"))
      (node (ref "E21") (pin "5") (pinfunction "I_5") (pintype "input"))
    )
    (net (code "237") (name "~{BTP3}") (class "Default")
      (node (ref "E19") (pin "12") (pinfunction "I1_12") (pintype "input"))
      (node (ref "E19") (pin "3") (pinfunction "I1_3") (pintype "input"))
      (node (ref "E21") (pin "4") (pinfunction "O_4") (pintype "output"))
      (node (ref "J") (pin "U1") (pinfunction "P_U1") (pintype "passive"))
    )
    (net (code "238") (name "~{B_IO_PAUSE}") (class "Default")
      (node (ref "E1") (pin "11") (pinfunction "I5_11") (pintype "input"))
      (node (ref "E34") (pin "1") (pinfunction "O_1") (pintype "output"))
    )
    (net (code "239") (name "~{C0}") (class "Default")
      (node (ref "E29") (pin "4") (pinfunction "F1_4") (pintype "open_collector"))
      (node (ref "OMNIBUS") (pin "CE1") (pinfunction "1_CE1") (pintype "bidirectional"))
    )
    (net (code "240") (name "~{C1}") (class "Default")
      (node (ref "E29") (pin "3") (pinfunction "F0_3") (pintype "open_collector"))
      (node (ref "OMNIBUS") (pin "CH1") (pinfunction "1_CH1") (pintype "bidirectional"))
    )
    (net (code "241") (name "~{CLR_ALL}") (class "Default")
      (node (ref "E12") (pin "6") (pinfunction "CL_6") (pintype "input"))
      (node (ref "E14") (pin "3") (pinfunction "CLR_3") (pintype "input"))
      (node (ref "E33") (pin "6") (pinfunction "O_6") (pintype "output"))
      (node (ref "J") (pin "U2") (pinfunction "P_U2") (pintype "passive"))
    )
    (net (code "242") (name "~{CLR_DRIVE_CMD}") (class "Default")
      (node (ref "E44") (pin "6") (pinfunction "O_6") (pintype "output"))
      (node (ref "E54") (pin "4") (pinfunction "I0_4") (pintype "input"))
      (node (ref "J") (pin "C2") (pinfunction "P_C2") (pintype "passive"))
    )
    (net (code "243") (name "~{CLR_STATUS}") (class "Default")
      (node (ref "E39") (pin "1") (pinfunction "CLR_1") (pintype "input"))
      (node (ref "E39") (pin "10") (pinfunction "PRE_10") (pintype "input"))
      (node (ref "E48") (pin "6") (pinfunction "O_6") (pintype "output"))
      (node (ref "E50") (pin "16") (pinfunction "CLR_16") (pintype "input"))
      (node (ref "E52") (pin "1") (pinfunction "CLR_1") (pintype "input"))
    )
    (net (code "244") (name "~{CLR_SYN}") (class "Default")
      (node (ref "E34") (pin "9") (pinfunction "I1_9") (pintype "input"))
      (node (ref "E52") (pin "9") (pinfunction "Q_9") (pintype "output"))
    )
    (net (code "245") (name "~{DATA0}") (class "Default")
      (node (ref "E8") (pin "3") (pinfunction "F0_3") (pintype "open_collector"))
      (node (ref "OMNIBUS") (pin "AR1") (pinfunction "1_AR1") (pintype "bidirectional"))
    )
    (net (code "246") (name "~{DATA1}") (class "Default")
      (node (ref "E8") (pin "4") (pinfunction "F1_4") (pintype "open_collector"))
      (node (ref "OMNIBUS") (pin "AS1") (pinfunction "1_AS1") (pintype "bidirectional"))
    )
    (net (code "247") (name "~{DATA2}") (class "Default")
      (node (ref "E8") (pin "12") (pinfunction "F2_12") (pintype "open_collector"))
      (node (ref "OMNIBUS") (pin "AU1") (pinfunction "1_AU1") (pintype "bidirectional"))
    )
    (net (code "248") (name "~{DATA3}") (class "Default")
      (node (ref "E8") (pin "13") (pinfunction "F3_13") (pintype "open_collector"))
      (node (ref "OMNIBUS") (pin "AV1") (pinfunction "1_AV1") (pintype "bidirectional"))
    )
    (net (code "249") (name "~{DATA4}") (class "Default")
      (node (ref "E22") (pin "3") (pinfunction "F0_3") (pintype "open_collector"))
      (node (ref "OMNIBUS") (pin "BR1") (pinfunction "1_BR1") (pintype "bidirectional"))
    )
    (net (code "250") (name "~{DATA5}") (class "Default")
      (node (ref "E22") (pin "4") (pinfunction "F1_4") (pintype "open_collector"))
      (node (ref "OMNIBUS") (pin "BS1") (pinfunction "1_BS1") (pintype "bidirectional"))
    )
    (net (code "251") (name "~{DATA6}") (class "Default")
      (node (ref "E22") (pin "12") (pinfunction "F2_12") (pintype "open_collector"))
      (node (ref "OMNIBUS") (pin "BU1") (pinfunction "1_BU1") (pintype "bidirectional"))
    )
    (net (code "252") (name "~{DATA7}") (class "Default")
      (node (ref "E22") (pin "13") (pinfunction "F3_13") (pintype "open_collector"))
      (node (ref "E35") (pin "12") (pinfunction "I1_12") (pintype "input"))
      (node (ref "OMNIBUS") (pin "BV1") (pinfunction "1_BV1") (pintype "bidirectional"))
    )
    (net (code "253") (name "~{DATA8}") (class "Default")
      (node (ref "E49") (pin "3") (pinfunction "F0_3") (pintype "open_collector"))
      (node (ref "OMNIBUS") (pin "DR1") (pinfunction "1_DR1") (pintype "bidirectional"))
    )
    (net (code "254") (name "~{DATA9}") (class "Default")
      (node (ref "E49") (pin "4") (pinfunction "F1_4") (pintype "open_collector"))
      (node (ref "OMNIBUS") (pin "DS1") (pinfunction "1_DS1") (pintype "bidirectional"))
    )
    (net (code "255") (name "~{DATA10}") (class "Default")
      (node (ref "E49") (pin "12") (pinfunction "F2_12") (pintype "open_collector"))
      (node (ref "OMNIBUS") (pin "DU1") (pinfunction "1_DU1") (pintype "bidirectional"))
    )
    (net (code "256") (name "~{DATA11}") (class "Default")
      (node (ref "E49") (pin "13") (pinfunction "F3_13") (pintype "open_collector"))
      (node (ref "OMNIBUS") (pin "DV1") (pinfunction "1_DV1") (pintype "bidirectional"))
    )
    (net (code "257") (name "~{DATA_RQST_LATE}") (class "Default")
      (node (ref "E39") (pin "6") (pinfunction "~{Q}_6") (pintype "output"))
      (node (ref "E47") (pin "9") (pinfunction "I0_9") (pintype "input"))
    )
    (net (code "258") (name "~{DATA_STATE}") (class "Default")
      (node (ref "E47") (pin "13") (pinfunction "I2_13") (pintype "input"))
      (node (ref "J") (pin "M2") (pinfunction "P_M2") (pintype "passive"))
    )
    (net (code "259") (name "~{DB_CONT1}") (class "Default")
      (node (ref "E12") (pin "13") (pinfunction "~{Q}_13") (pintype "output"))
      (node (ref "E13") (pin "6") (pinfunction "I1_6") (pintype "input"))
      (node (ref "H") (pin "V1") (pinfunction "P_V1") (pintype "passive"))
    )
    (net (code "260") (name "~{DB_CONT2}") (class "Default")
      (node (ref "E12") (pin "8") (pinfunction "~{Q}_8") (pintype "output"))
      (node (ref "E13") (pin "9") (pinfunction "I1_9") (pintype "input"))
      (node (ref "E28") (pin "3") (pinfunction "I1_3") (pintype "input"))
    )
    (net (code "261") (name "~{DB_CONT3}") (class "Default")
      (node (ref "E13") (pin "11") (pinfunction "I0_11") (pintype "input"))
      (node (ref "E14") (pin "14") (pinfunction "~{Q}_14") (pintype "output"))
    )
    (net (code "262") (name "~{DB_CONT4}") (class "Default")
      (node (ref "C56") (pin "1") (pinfunction "1_1") (pintype "passive"))
      (node (ref "E17") (pin "6") (pinfunction "MOD_6") (pintype "input"))
      (node (ref "E24") (pin "6") (pinfunction "MOD_6") (pintype "input"))
      (node (ref "E39") (pin "2") (pinfunction "D_2") (pintype "input"))
      (node (ref "E9") (pin "6") (pinfunction "MOD_6") (pintype "input"))
      (node (ref "R15") (pin "2") (pinfunction "2_2") (pintype "passive"))
    )
    (net (code "263") (name "~{DEVICE_RK}") (class "Default")
      (node (ref "E31") (pin "4") (pinfunction "O_4") (pintype "output"))
      (node (ref "E37") (pin "2") (pinfunction "D_2") (pintype "input"))
    )
    (net (code "264") (name "~{DONE_FLAG}") (class "Default")
      (node (ref "E39") (pin "9") (pinfunction "Q_9") (pintype "output"))
      (node (ref "E54") (pin "2") (pinfunction "I1_2") (pintype "input"))
    )
    (net (code "265") (name "~{DSK_CAPACITY_EX}") (class "Default")
      (node (ref "E45") (pin "12") (pinfunction "I0_12") (pintype "input"))
      (node (ref "J") (pin "K1") (pinfunction "P_K1") (pintype "passive"))
      (node (ref "R1") (pin "2") (pinfunction "2_2") (pintype "passive"))
      (node (ref "R2") (pin "1") (pinfunction "1_1") (pintype "passive"))
    )
    (net (code "266") (name "~{DSK_FILE_RDY}") (class "Default")
      (node (ref "E22") (pin "1") (pinfunction "A0_1") (pintype "input"))
      (node (ref "H") (pin "E1") (pinfunction "P_E1") (pintype "passive"))
    )
    (net (code "267") (name "~{ENAB_RK_DATA}") (class "Default")
      (node (ref "E22") (pin "9") (pinfunction "S0_9") (pintype "input"))
      (node (ref "E31") (pin "6") (pinfunction "O_6") (pintype "output"))
      (node (ref "E49") (pin "9") (pinfunction "S0_9") (pintype "input"))
      (node (ref "E8") (pin "9") (pinfunction "S0_9") (pintype "input"))
    )
    (net (code "268") (name "~{END_STATE}") (class "Default")
      (node (ref "E51") (pin "6") (pinfunction "I1_6") (pintype "input"))
      (node (ref "J") (pin "J2") (pinfunction "P_J2") (pintype "passive"))
    )
    (net (code "269") (name "~{ERROR_CLR}") (class "Default")
      (node (ref "E53") (pin "13") (pinfunction "O_13") (pintype "output"))
      (node (ref "J") (pin "D1") (pinfunction "P_D1") (pintype "passive"))
    )
    (net (code "270") (name "~{ERROR_FL}") (class "Default")
      (node (ref "E53") (pin "10") (pinfunction "O_10") (pintype "output"))
      (node (ref "E54") (pin "1") (pinfunction "I0_1") (pintype "input"))
    )
    (net (code "271") (name "~{HI_RD_CLK}") (class "Default")
      (node (ref "E11") (pin "12") (pinfunction "I0_12") (pintype "input"))
      (node (ref "E27") (pin "10") (pinfunction "O_10") (pintype "output"))
    )
    (net (code "272") (name "~{IDLE}") (class "Default")
      (node (ref "E19") (pin "6") (pinfunction "I1_6") (pintype "input"))
      (node (ref "E48") (pin "10") (pinfunction "I1_10") (pintype "input"))
      (node (ref "J") (pin "N1") (pinfunction "P_N1") (pintype "passive"))
    )
    (net (code "273") (name "~{INTERNAL_IO}") (class "Default")
      (node (ref "E36") (pin "10") (pinfunction "O_10") (pintype "open_collector"))
      (node (ref "OMNIBUS") (pin "CL1") (pinfunction "1_CL1") (pintype "bidirectional"))
    )
    (net (code "274") (name "~{INT_RQST}") (class "Default")
      (node (ref "E36") (pin "4") (pinfunction "O_4") (pintype "open_collector"))
      (node (ref "OMNIBUS") (pin "CP1") (pinfunction "1_CP1") (pintype "bidirectional"))
    )
    (net (code "275") (name "~{IO_PAUSE}") (class "Default")
      (node (ref "E35") (pin "10") (pinfunction "I1_10") (pintype "input"))
      (node (ref "OMNIBUS") (pin "CD1") (pinfunction "1_CD1") (pintype "bidirectional"))
    )
    (net (code "276") (name "~{LD_DB_AC}") (class "Default")
      (node (ref "E21") (pin "9") (pinfunction "I_9") (pintype "input"))
      (node (ref "E33") (pin "13") (pinfunction "I1_13") (pintype "input"))
      (node (ref "E40") (pin "10") (pinfunction "I1_10") (pintype "input"))
      (node (ref "E54") (pin "11") (pinfunction "O_11") (pintype "output"))
    )
    (net (code "277") (name "~{LO_MAIN_SHFT}") (class "Default")
      (node (ref "E20") (pin "1") (pinfunction "I0_1") (pintype "input"))
      (node (ref "H") (pin "P1") (pinfunction "P_P1") (pintype "passive"))
    )
    (net (code "278") (name "~{MAIN}") (class "Default")
      (node (ref "E40") (pin "1") (pinfunction "I0_1") (pintype "input"))
      (node (ref "E47") (pin "1") (pinfunction "I0_1") (pintype "input"))
      (node (ref "J") (pin "E1") (pinfunction "P_E1") (pintype "passive"))
    )
    (net (code "279") (name "~{MAK}") (class "Default")
      (node (ref "E28") (pin "12") (pinfunction "I1_12") (pintype "input"))
      (node (ref "H") (pin "J1") (pinfunction "P_J1") (pintype "passive"))
    )
    (net (code "280") (name "~{MD0}") (class "Default")
      (node (ref "E2") (pin "7") (pinfunction "I1_7") (pintype "input"))
      (node (ref "OMNIBUS") (pin "AK1") (pinfunction "1_AK1") (pintype "bidirectional"))
    )
    (net (code "281") (name "~{MD1}") (class "Default")
      (node (ref "E2") (pin "9") (pinfunction "I0_9") (pintype "input"))
      (node (ref "OMNIBUS") (pin "AL1") (pinfunction "1_AL1") (pintype "bidirectional"))
    )
    (net (code "282") (name "~{MD2}") (class "Default")
      (node (ref "E2") (pin "4") (pinfunction "I0_4") (pintype "input"))
      (node (ref "OMNIBUS") (pin "AM1") (pinfunction "1_AM1") (pintype "bidirectional"))
    )
    (net (code "283") (name "~{MD3}") (class "Default")
      (node (ref "E1") (pin "12") (pinfunction "I6_12") (pintype "input"))
      (node (ref "E2") (pin "12") (pinfunction "I1_12") (pintype "input"))
      (node (ref "OMNIBUS") (pin "AP1") (pinfunction "1_AP1") (pintype "bidirectional"))
    )
    (net (code "284") (name "~{MD4}") (class "Default")
      (node (ref "E1") (pin "10") (pinfunction "I4_10") (pintype "input"))
      (node (ref "E15") (pin "7") (pinfunction "I1_7") (pintype "input"))
      (node (ref "OMNIBUS") (pin "BK1") (pinfunction "1_BK1") (pintype "bidirectional"))
    )
    (net (code "285") (name "~{MD5}") (class "Default")
      (node (ref "E1") (pin "9") (pinfunction "I3_9") (pintype "input"))
      (node (ref "E15") (pin "9") (pinfunction "I0_9") (pintype "input"))
      (node (ref "OMNIBUS") (pin "BL1") (pinfunction "1_BL1") (pintype "bidirectional"))
    )
    (net (code "286") (name "~{MD6}") (class "Default")
      (node (ref "E15") (pin "4") (pinfunction "I0_4") (pintype "input"))
      (node (ref "OMNIBUS") (pin "BM1") (pinfunction "1_BM1") (pintype "bidirectional"))
      (node (ref "W2W5") (pin "1") (pinfunction "1_1") (pintype "passive"))
    )
    (net (code "287") (name "~{MD7}") (class "Default")
      (node (ref "E15") (pin "12") (pinfunction "I1_12") (pintype "input"))
      (node (ref "OMNIBUS") (pin "BP1") (pinfunction "1_BP1") (pintype "bidirectional"))
      (node (ref "W1W4") (pin "3") (pinfunction "3_3") (pintype "passive"))
    )
    (net (code "288") (name "~{MD8}") (class "Default")
      (node (ref "E42") (pin "7") (pinfunction "I1_7") (pintype "input"))
      (node (ref "OMNIBUS") (pin "DK1") (pinfunction "1_DK1") (pintype "bidirectional"))
      (node (ref "W3W6") (pin "3") (pinfunction "3_3") (pintype "passive"))
    )
    (net (code "289") (name "~{MD9}") (class "Default")
      (node (ref "E42") (pin "9") (pinfunction "I0_9") (pintype "input"))
      (node (ref "OMNIBUS") (pin "DL1") (pinfunction "1_DL1") (pintype "bidirectional"))
    )
    (net (code "290") (name "~{MD10}") (class "Default")
      (node (ref "E42") (pin "4") (pinfunction "I0_4") (pintype "input"))
      (node (ref "OMNIBUS") (pin "DM1") (pinfunction "1_DM1") (pintype "bidirectional"))
    )
    (net (code "291") (name "~{MD11}") (class "Default")
      (node (ref "E42") (pin "12") (pinfunction "I1_12") (pintype "input"))
      (node (ref "OMNIBUS") (pin "DP1") (pinfunction "1_DP1") (pintype "bidirectional"))
    )
    (net (code "292") (name "~{MD_RD_BUFF}") (class "Default")
      (node (ref "E15") (pin "10") (pinfunction "I1_10") (pintype "input"))
      (node (ref "E15") (pin "6") (pinfunction "I0_6") (pintype "input"))
      (node (ref "E19") (pin "11") (pinfunction "I0_11") (pintype "input"))
      (node (ref "E2") (pin "10") (pinfunction "I1_10") (pintype "input"))
      (node (ref "E2") (pin "11") (pinfunction "I0_11") (pintype "input"))
      (node (ref "E2") (pin "5") (pinfunction "I1_5") (pintype "input"))
      (node (ref "E2") (pin "6") (pinfunction "I0_6") (pintype "input"))
      (node (ref "E20") (pin "6") (pinfunction "O_6") (pintype "output"))
      (node (ref "E27") (pin "3") (pinfunction "I_3") (pintype "input"))
      (node (ref "E47") (pin "2") (pinfunction "I1_2") (pintype "input"))
      (node (ref "R9") (pin "1") (pinfunction "1_1") (pintype "passive"))
    )
    (net (code "293") (name "~{MD_RK}") (class "Default")
      (node (ref "E42") (pin "10") (pinfunction "I1_10") (pintype "input"))
      (node (ref "E42") (pin "11") (pinfunction "I0_11") (pintype "input"))
      (node (ref "E42") (pin "5") (pinfunction "I1_5") (pintype "input"))
      (node (ref "E51") (pin "1") (pinfunction "O_1") (pintype "output"))
      (node (ref "R11") (pin "1") (pinfunction "1_1") (pintype "passive"))
    )
    (net (code "294") (name "~{NOT_EQ}") (class "Default")
      (node (ref "E51") (pin "5") (pinfunction "I0_5") (pintype "input"))
      (node (ref "E51") (pin "8") (pinfunction "I0_8") (pintype "input"))
      (node (ref "J") (pin "F2") (pinfunction "P_F2") (pintype "passive"))
    )
    (net (code "295") (name "~{RDY_S{slash}R{slash}W}") (class "Default")
      (node (ref "E8") (pin "6") (pinfunction "A1_6") (pintype "input"))
      (node (ref "H") (pin "U1") (pinfunction "P_U1") (pintype "passive"))
    )
    (net (code "296") (name "~{RD_BRK}") (class "Default")
      (node (ref "E28") (pin "9") (pinfunction "I1_9") (pintype "input"))
      (node (ref "H") (pin "L2") (pinfunction "P_L2") (pintype "passive"))
    )
    (net (code "297") (name "~{RK_DATA0}") (class "Default")
      (node (ref "E16") (pin "6") (pinfunction "O_6") (pintype "output"))
      (node (ref "E8") (pin "2") (pinfunction "B0_2") (pintype "input"))
    )
    (net (code "298") (name "~{RK_DATA1}") (class "Default")
      (node (ref "E16") (pin "4") (pinfunction "O_4") (pintype "output"))
      (node (ref "E8") (pin "5") (pinfunction "B1_5") (pintype "input"))
    )
    (net (code "299") (name "~{RK_DATA2}") (class "Default")
      (node (ref "E16") (pin "10") (pinfunction "O_10") (pintype "output"))
      (node (ref "E8") (pin "11") (pinfunction "B2_11") (pintype "input"))
    )
    (net (code "300") (name "~{RK_DATA3}") (class "Default")
      (node (ref "E16") (pin "8") (pinfunction "O_8") (pintype "output"))
      (node (ref "E8") (pin "14") (pinfunction "B3_14") (pintype "input"))
    )
    (net (code "301") (name "~{RK_DATA4}") (class "Default")
      (node (ref "E22") (pin "2") (pinfunction "B0_2") (pintype "input"))
      (node (ref "E23") (pin "8") (pinfunction "O_8") (pintype "output"))
    )
    (net (code "302") (name "~{RK_DATA5}") (class "Default")
      (node (ref "E16") (pin "12") (pinfunction "O_12") (pintype "output"))
      (node (ref "E22") (pin "5") (pinfunction "B1_5") (pintype "input"))
    )
    (net (code "303") (name "~{RK_DATA6}") (class "Default")
      (node (ref "E16") (pin "2") (pinfunction "O_2") (pintype "output"))
      (node (ref "E22") (pin "11") (pinfunction "B2_11") (pintype "input"))
    )
    (net (code "304") (name "~{RK_DATA7}") (class "Default")
      (node (ref "E22") (pin "14") (pinfunction "B3_14") (pintype "input"))
      (node (ref "E23") (pin "10") (pinfunction "O_10") (pintype "output"))
    )
    (net (code "305") (name "~{RK_DATA8}") (class "Default")
      (node (ref "E23") (pin "2") (pinfunction "O_2") (pintype "output"))
      (node (ref "E49") (pin "2") (pinfunction "B0_2") (pintype "input"))
    )
    (net (code "306") (name "~{RK_DATA9}") (class "Default")
      (node (ref "E23") (pin "6") (pinfunction "O_6") (pintype "output"))
      (node (ref "E49") (pin "5") (pinfunction "B1_5") (pintype "input"))
    )
    (net (code "307") (name "~{RK_DATA10}") (class "Default")
      (node (ref "E23") (pin "4") (pinfunction "O_4") (pintype "output"))
      (node (ref "E49") (pin "11") (pinfunction "B2_11") (pintype "input"))
    )
    (net (code "308") (name "~{RK_DATA11}") (class "Default")
      (node (ref "E23") (pin "12") (pinfunction "O_12") (pintype "output"))
      (node (ref "E49") (pin "14") (pinfunction "B3_14") (pintype "input"))
    )
    (net (code "309") (name "~{SECTOR_SEEK}") (class "Default")
      (node (ref "E51") (pin "9") (pinfunction "I1_9") (pintype "input"))
      (node (ref "J") (pin "F1") (pinfunction "P_F1") (pintype "passive"))
    )
    (net (code "310") (name "~{SET_IDLE_PL}") (class "Default")
      (node (ref "E46") (pin "13") (pinfunction "I1_13") (pintype "input"))
      (node (ref "E46") (pin "3") (pinfunction "O_3") (pintype "output"))
      (node (ref "J") (pin "J1") (pinfunction "P_J1") (pintype "passive"))
    )
    (net (code "311") (name "~{SHFT_WRT_BUFF}") (class "Default")
      (node (ref "E20") (pin "2") (pinfunction "I1_2") (pintype "input"))
      (node (ref "H") (pin "R2") (pinfunction "P_R2") (pintype "passive"))
    )
    (net (code "312") (name "~{SKIP}") (class "Default")
      (node (ref "E36") (pin "1") (pinfunction "O_1") (pintype "open_collector"))
      (node (ref "OMNIBUS") (pin "CS1") (pinfunction "1_CS1") (pintype "bidirectional"))
    )
    (net (code "313") (name "~{TEST_CLK}") (class "Default")
      (node (ref "E7") (pin "12") (pinfunction "~{Q}_12") (pintype "output"))
      (node (ref "E7") (pin "2") (pinfunction "B_2") (pintype "input"))
    )
    (net (code "314") (name "~{TS3}") (class "Default")
      (node (ref "E35") (pin "9") (pinfunction "I0_9") (pintype "input"))
      (node (ref "OMNIBUS") (pin "CM2") (pinfunction "1_CM2") (pintype "bidirectional"))
    )
    (net (code "315") (name "~{WRT_BRK}") (class "Default")
      (node (ref "E28") (pin "2") (pinfunction "I0_2") (pintype "input"))
      (node (ref "H") (pin "H1") (pinfunction "P_H1") (pintype "passive"))
    )
    (net (code "316") (name "~{WRT_BUFF_SHFT}") (class "Default")
      (node (ref "E17") (pin "9") (pinfunction "CK1_9") (pintype "input"))
      (node (ref "E24") (pin "9") (pinfunction "CK1_9") (pintype "input"))
      (node (ref "E31") (pin "8") (pinfunction "O_8") (pintype "output"))
      (node (ref "E9") (pin "9") (pinfunction "CK1_9") (pintype "input"))
    )
    (net (code "317") (name "~{WRT_CMD}") (class "Default")
      (node (ref "E11") (pin "13") (pinfunction "I1_13") (pintype "input"))
      (node (ref "E11") (pin "2") (pinfunction "I1_2") (pintype "input"))
      (node (ref "E51") (pin "11") (pinfunction "I0_11") (pintype "input"))
      (node (ref "J") (pin "E2") (pinfunction "P_E2") (pintype "passive"))
    )
    (net (code "318") (name "~{WRT_LOCK_ER}") (class "Default")
      (node (ref "E52") (pin "6") (pinfunction "~{Q}_6") (pintype "output"))
    )
    (net (code "319") (name "~{WT_BUFF_DATA}") (class "Default")
      (node (ref "E21") (pin "13") (pinfunction "I_13") (pintype "input"))
      (node (ref "E33") (pin "12") (pinfunction "I0_12") (pintype "input"))
      (node (ref "H") (pin "D2") (pinfunction "P_D2") (pintype "passive"))
    )
  )
)
